# RUMBA_plus.net
KiCad netlist of a schematic drawn in Altium Designer
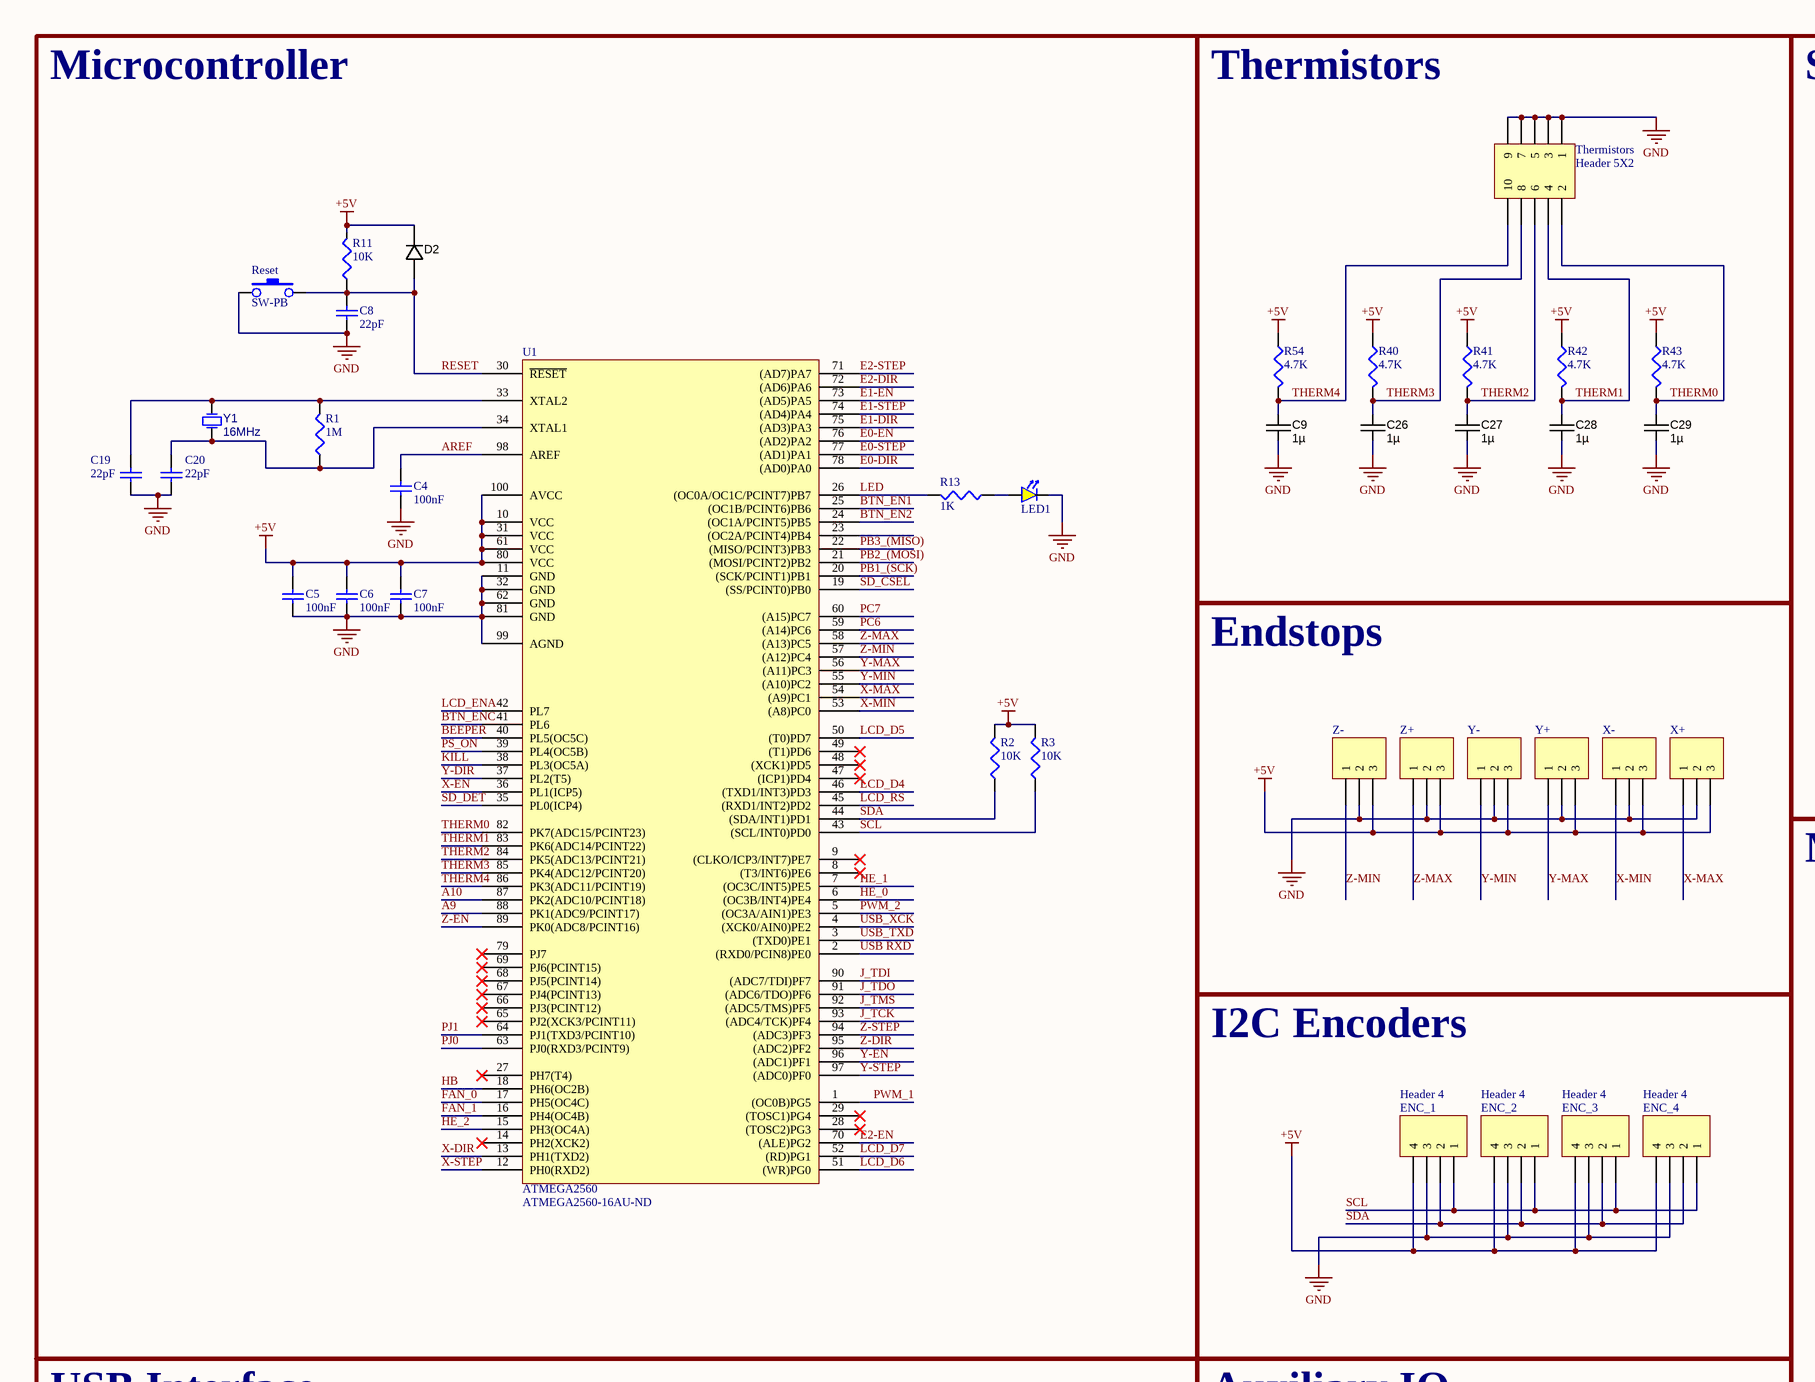
[diagram p0: RUMBA_plus.SchDoc, top left]
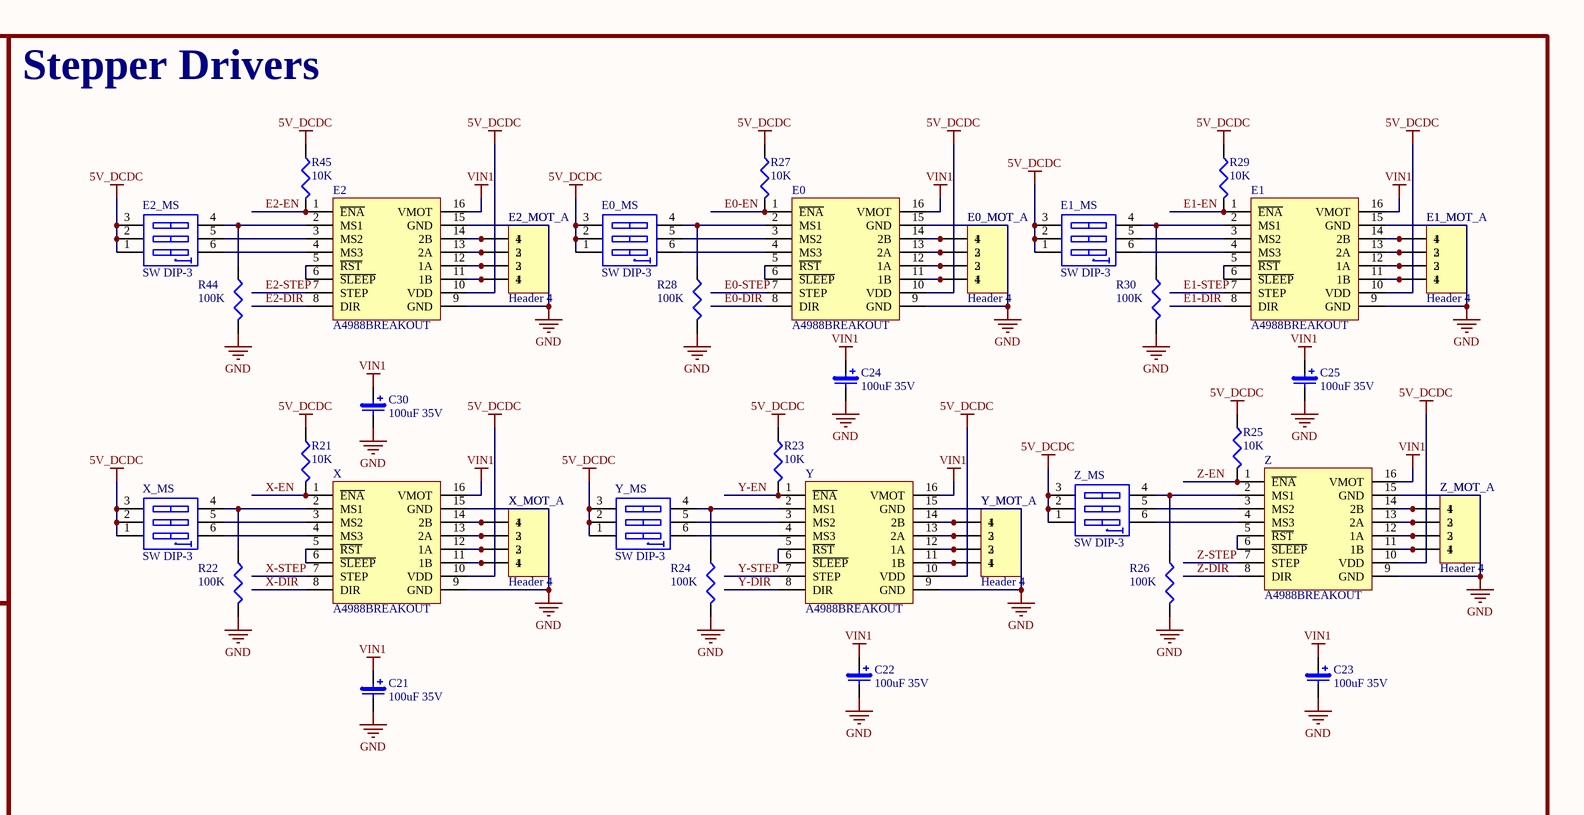
[diagram p1: RUMBA_plus.SchDoc, top right]
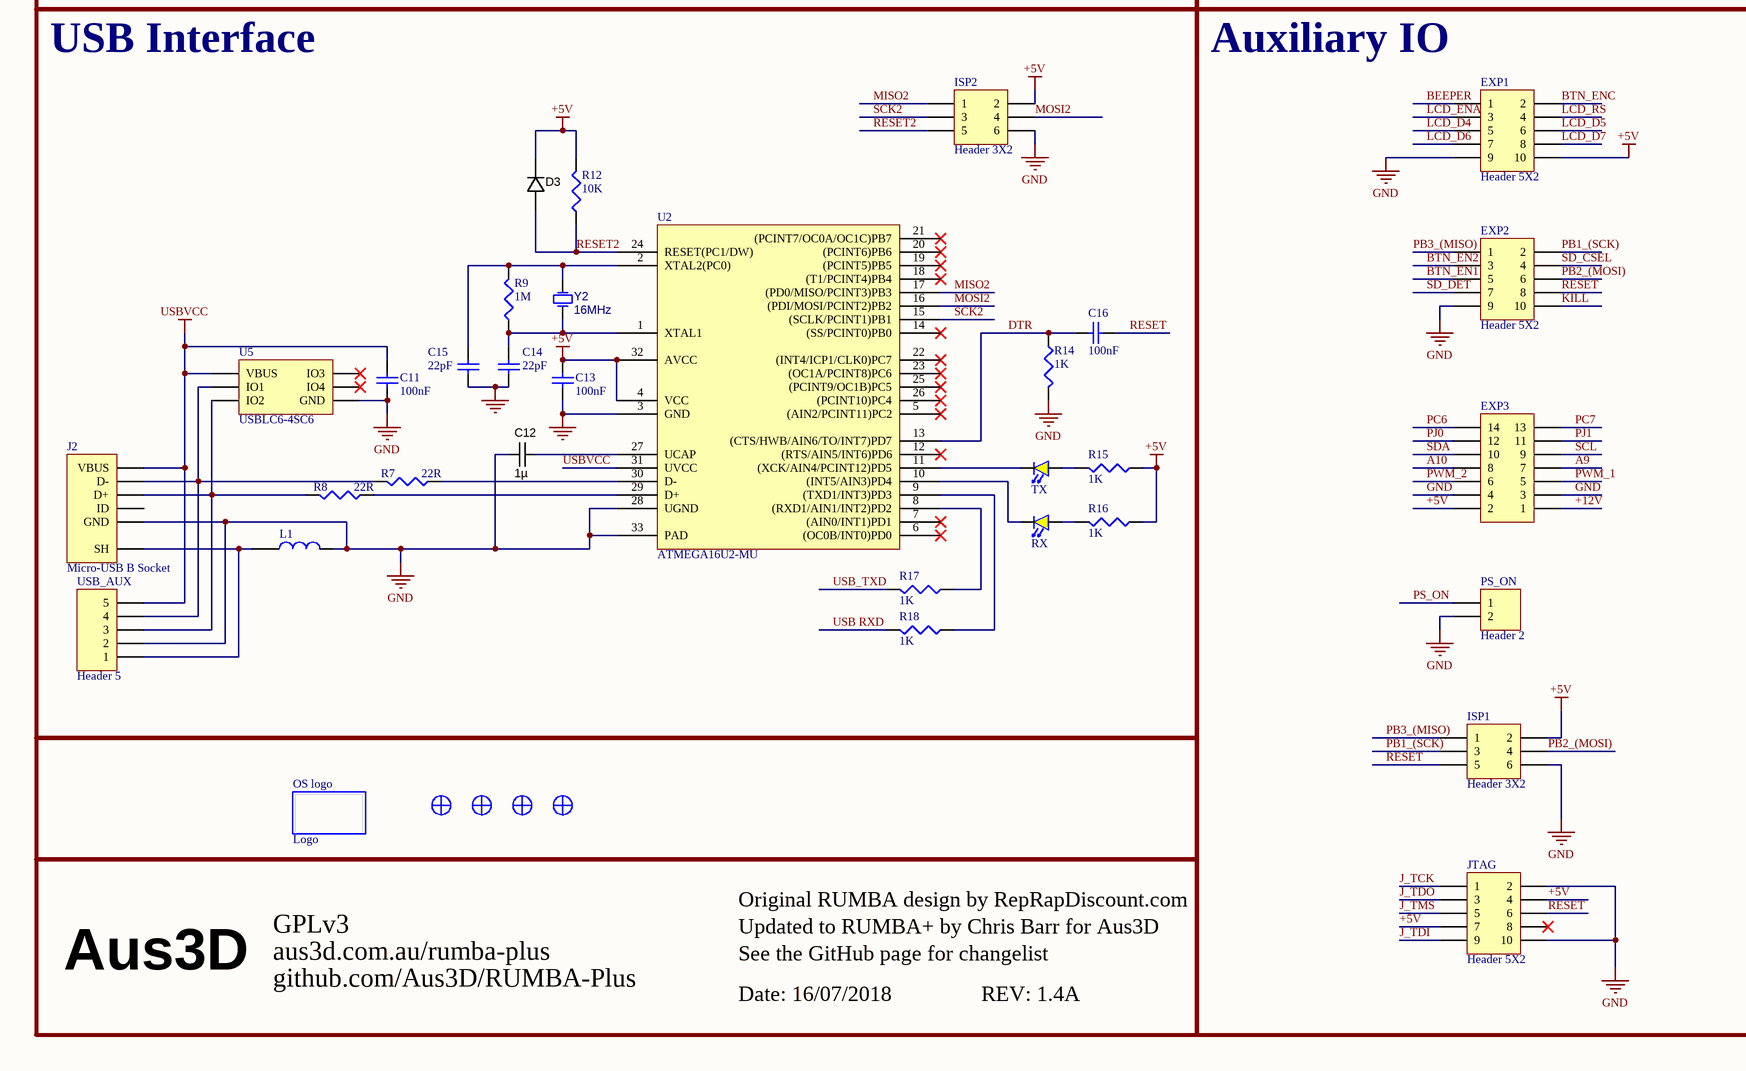
[diagram p2: RUMBA_plus.SchDoc, bottom left]
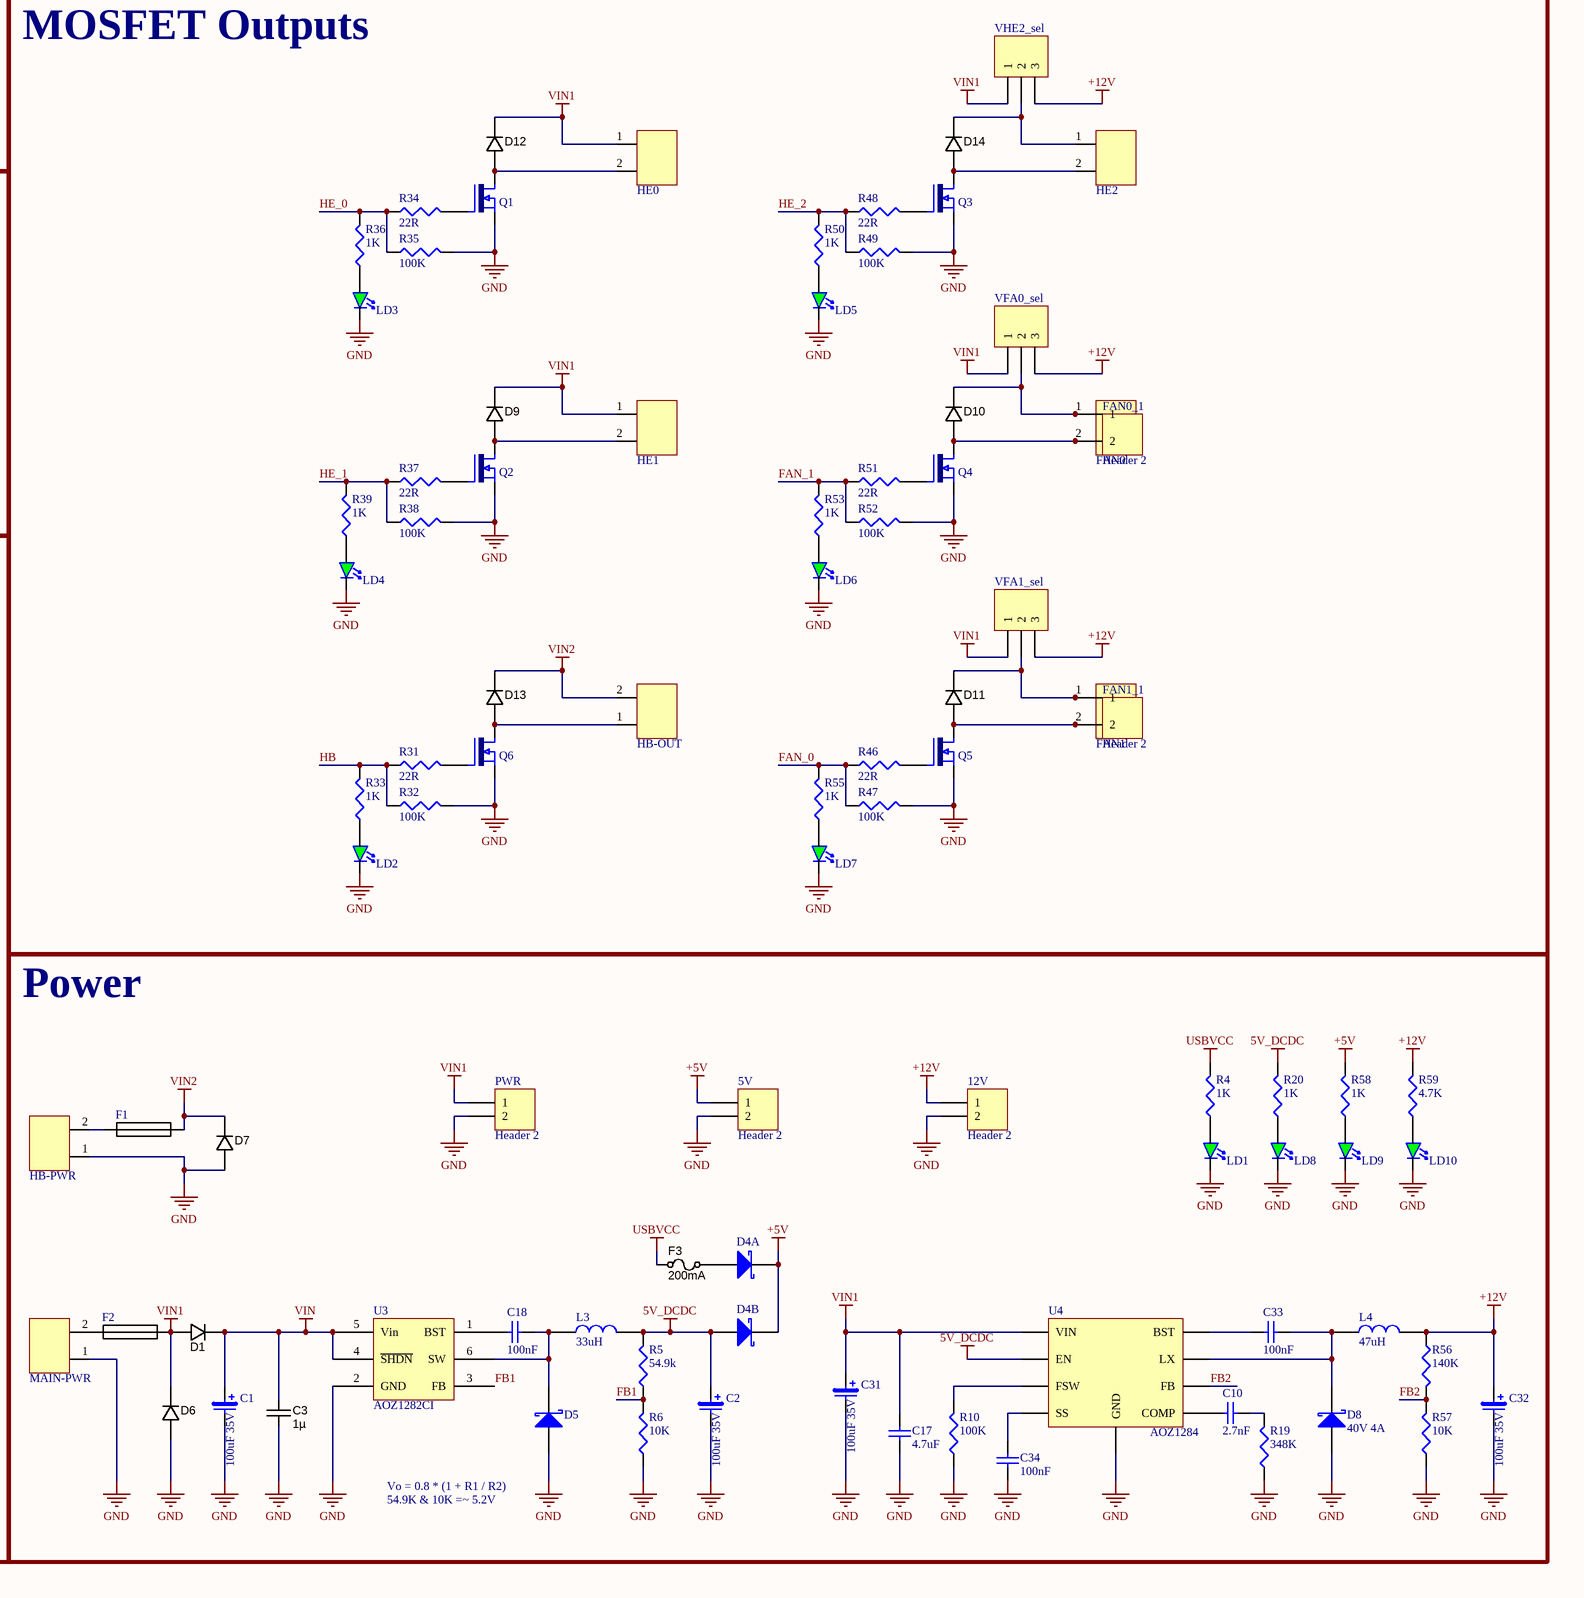
[diagram p3: RUMBA_plus.SchDoc, bottom right]

(export (version "E")
  (design (tool "Eeschema 10.0.6"))
  (components
    (comp (ref "5V")
      (value "Header 2")
      (footprint "HDR1X2")
      (description "Header, 2-Pin")
      (fields (field (name "PUBLISHER") "Altium Limited"))
      (libsource (lib "") (part "Header 2_1"))
    )
    (comp (ref "12V")
      (value "Header 2")
      (footprint "HDR1X2")
      (description "Header, 2-Pin")
      (fields (field (name "PUBLISHER") "Altium Limited"))
      (libsource (lib "") (part "Header 2_1"))
    )
    (comp (ref "C1")
      (value "100uF 35V")
      (footprint "CAP EL PANASONIC")
      (description "Polarized Capacitor (Surface Mount)")
      (fields (field (name "Comment") "CapE-6.3-100uF-35V") (field (name "PUBLISHER") "Altium Limited"))
      (libsource (lib "RUMBA_v2") (part "CapE-6.3-100uF-35V"))
    )
    (comp (ref "C2")
      (value "100uF 35V")
      (footprint "CAP EL PANASONIC")
      (description "Polarized Capacitor (Surface Mount)")
      (fields (field (name "Comment") "CapE-6.3-100uF-35V") (field (name "PUBLISHER") "Altium Limited"))
      (libsource (lib "RUMBA_v2") (part "CapE-6.3-100uF-35V"))
    )
    (comp (ref "C3")
      (value "1µ")
      (footprint "Cap 1608-0603")
      (description "Capacitor SMD Cer 1uF 10% 16V X7R 0603")
      (fields (field (name "TOLERANCE") "±10%") (field (name "Comment") "approved sub OK"))
      (libsource (lib "PBL - Capacitors") (part "CAPC_1u_0603_X7R_16V_10%"))
    )
    (comp (ref "C4")
      (value "100nF")
      (footprint "Cap 1608-0603")
      (description "Capacitor (Semiconductor SIM Model)")
      (fields (field (name "Comment") "CapC-0603-100nF") (field (name "PUBLISHER") "Altium Limited"))
      (libsource (lib "RUMBA_v2") (part "CapC-0603-100nF"))
    )
    (comp (ref "C5")
      (value "100nF")
      (footprint "Cap 1608-0603")
      (description "Capacitor (Semiconductor SIM Model)")
      (fields (field (name "Comment") "CapC-0603-100nF") (field (name "PUBLISHER") "Altium Limited"))
      (libsource (lib "RUMBA_v2") (part "CapC-0603-100nF"))
    )
    (comp (ref "C6")
      (value "100nF")
      (footprint "Cap 1608-0603")
      (description "Capacitor (Semiconductor SIM Model)")
      (fields (field (name "Comment") "CapC-0603-100nF") (field (name "PUBLISHER") "Altium Limited"))
      (libsource (lib "RUMBA_v2") (part "CapC-0603-100nF"))
    )
    (comp (ref "C7")
      (value "100nF")
      (footprint "Cap 1608-0603")
      (description "Capacitor (Semiconductor SIM Model)")
      (fields (field (name "Comment") "CapC-0603-100nF") (field (name "PUBLISHER") "Altium Limited"))
      (libsource (lib "RUMBA_v2") (part "CapC-0603-100nF"))
    )
    (comp (ref "C8")
      (value "22pF")
      (footprint "Cap 1608-0603")
      (description "Capacitor (Semiconductor SIM Model)")
      (fields (field (name "Comment") "CapC-0603-22pF") (field (name "PUBLISHER") "Altium Limited"))
      (libsource (lib "RUMBA_v2") (part "CapC-0603-22pF"))
    )
    (comp (ref "C9")
      (value "1µ")
      (footprint "Cap 1608-0603")
      (description "Capacitor SMD Cer 1uF 10% 16V X7R 0603")
      (fields (field (name "TOLERANCE") "±10%") (field (name "Comment") "approved sub OK"))
      (libsource (lib "PBL - Capacitors") (part "CAPC_1u_0603_X7R_16V_10%"))
    )
    (comp (ref "C10")
      (value "2.7nF")
      (footprint "Cap 1608-0603")
      (description "Capacitor (Semiconductor SIM Model)")
      (fields (field (name "Comment") "CapC-0603-2.7nF") (field (name "PUBLISHER") "Altium Limited"))
      (libsource (lib "RUMBA_v2") (part "CapC-0603-100nF"))
    )
    (comp (ref "C11")
      (value "100nF")
      (footprint "Cap 1608-0603")
      (description "Capacitor (Semiconductor SIM Model)")
      (fields (field (name "Comment") "CapC-0603-100nF") (field (name "PUBLISHER") "Altium Limited"))
      (libsource (lib "RUMBA_v2") (part "CapC-0603-100nF"))
    )
    (comp (ref "C12")
      (value "1µ")
      (footprint "Cap 1608-0603")
      (description "Capacitor SMD Cer 1uF 10% 16V X7R 0603")
      (fields (field (name "TOLERANCE") "±10%") (field (name "Comment") "approved sub OK"))
      (libsource (lib "PBL - Capacitors") (part "CAPC_1u_0603_X7R_16V_10%"))
    )
    (comp (ref "C13")
      (value "100nF")
      (footprint "Cap 1608-0603")
      (description "Capacitor (Semiconductor SIM Model)")
      (fields (field (name "Comment") "CapC-0603-100nF") (field (name "PUBLISHER") "Altium Limited"))
      (libsource (lib "RUMBA_v2") (part "CapC-0603-100nF"))
    )
    (comp (ref "C14")
      (value "22pF")
      (footprint "Cap 1608-0603")
      (description "Capacitor (Semiconductor SIM Model)")
      (fields (field (name "Comment") "CapC-0603-22pF") (field (name "PUBLISHER") "Altium Limited"))
      (libsource (lib "RUMBA_v2") (part "CapC-0603-22pF"))
    )
    (comp (ref "C15")
      (value "22pF")
      (footprint "Cap 1608-0603")
      (description "Capacitor (Semiconductor SIM Model)")
      (fields (field (name "Comment") "CapC-0603-22pF") (field (name "PUBLISHER") "Altium Limited"))
      (libsource (lib "RUMBA_v2") (part "CapC-0603-22pF"))
    )
    (comp (ref "C16")
      (value "100nF")
      (footprint "Cap 1608-0603")
      (description "Capacitor (Semiconductor SIM Model)")
      (fields (field (name "Comment") "CapC-0603-100nF") (field (name "PUBLISHER") "Altium Limited"))
      (libsource (lib "RUMBA_v2") (part "CapC-0603-100nF"))
    )
    (comp (ref "C17")
      (value "4.7uF")
      (footprint "CAP 3225-1210")
      (description "Capacitor (Semiconductor SIM Model)")
      (fields (field (name "Comment") "CapC-1210-4.7uF-50V") (field (name "PUBLISHER") "Altium Limited"))
      (libsource (lib "picoprint_library") (part "CapC-1210-4.7uF-50V"))
    )
    (comp (ref "C18")
      (value "100nF")
      (footprint "Cap 1608-0603")
      (description "Capacitor (Semiconductor SIM Model)")
      (fields (field (name "Comment") "CapC-0603-100nF") (field (name "PUBLISHER") "Altium Limited"))
      (libsource (lib "RUMBA_v2") (part "CapC-0603-100nF"))
    )
    (comp (ref "C19")
      (value "22pF")
      (footprint "Cap 1608-0603")
      (description "Capacitor (Semiconductor SIM Model)")
      (fields (field (name "Comment") "CapC-0603-22pF") (field (name "PUBLISHER") "Altium Limited"))
      (libsource (lib "RUMBA_v2") (part "CapC-0603-22pF"))
    )
    (comp (ref "C20")
      (value "22pF")
      (footprint "Cap 1608-0603")
      (description "Capacitor (Semiconductor SIM Model)")
      (fields (field (name "Comment") "CapC-0603-22pF") (field (name "PUBLISHER") "Altium Limited"))
      (libsource (lib "RUMBA_v2") (part "CapC-0603-22pF"))
    )
    (comp (ref "C21")
      (value "100uF 35V")
      (footprint "CAP EL PANASONIC")
      (description "Polarized Capacitor (Surface Mount)")
      (fields (field (name "Comment") "CapE-6.3-100uF-35V") (field (name "PUBLISHER") "Altium Limited"))
      (libsource (lib "RUMBA_v2") (part "CapE-6.3-100uF-35V"))
    )
    (comp (ref "C22")
      (value "100uF 35V")
      (footprint "CAP EL PANASONIC")
      (description "Polarized Capacitor (Surface Mount)")
      (fields (field (name "Comment") "CapE-6.3-100uF-35V") (field (name "PUBLISHER") "Altium Limited"))
      (libsource (lib "RUMBA_v2") (part "CapE-6.3-100uF-35V"))
    )
    (comp (ref "C23")
      (value "100uF 35V")
      (footprint "CAP EL PANASONIC")
      (description "Polarized Capacitor (Surface Mount)")
      (fields (field (name "Comment") "CapE-6.3-100uF-35V") (field (name "PUBLISHER") "Altium Limited"))
      (libsource (lib "RUMBA_v2") (part "CapE-6.3-100uF-35V"))
    )
    (comp (ref "C24")
      (value "100uF 35V")
      (footprint "CAP EL PANASONIC")
      (description "Polarized Capacitor (Surface Mount)")
      (fields (field (name "Comment") "CapE-6.3-100uF-35V") (field (name "PUBLISHER") "Altium Limited"))
      (libsource (lib "RUMBA_v2") (part "CapE-6.3-100uF-35V"))
    )
    (comp (ref "C25")
      (value "100uF 35V")
      (footprint "CAP EL PANASONIC")
      (description "Polarized Capacitor (Surface Mount)")
      (fields (field (name "Comment") "CapE-6.3-100uF-35V") (field (name "PUBLISHER") "Altium Limited"))
      (libsource (lib "RUMBA_v2") (part "CapE-6.3-100uF-35V"))
    )
    (comp (ref "C26")
      (value "1µ")
      (footprint "Cap 1608-0603")
      (description "Capacitor SMD Cer 1uF 10% 16V X7R 0603")
      (fields (field (name "TOLERANCE") "±10%") (field (name "Comment") "approved sub OK"))
      (libsource (lib "PBL - Capacitors") (part "CAPC_1u_0603_X7R_16V_10%"))
    )
    (comp (ref "C27")
      (value "1µ")
      (footprint "Cap 1608-0603")
      (description "Capacitor SMD Cer 1uF 10% 16V X7R 0603")
      (fields (field (name "TOLERANCE") "±10%") (field (name "Comment") "approved sub OK"))
      (libsource (lib "PBL - Capacitors") (part "CAPC_1u_0603_X7R_16V_10%"))
    )
    (comp (ref "C28")
      (value "1µ")
      (footprint "Cap 1608-0603")
      (description "Capacitor SMD Cer 1uF 10% 16V X7R 0603")
      (fields (field (name "TOLERANCE") "±10%") (field (name "Comment") "approved sub OK"))
      (libsource (lib "PBL - Capacitors") (part "CAPC_1u_0603_X7R_16V_10%"))
    )
    (comp (ref "C29")
      (value "1µ")
      (footprint "Cap 1608-0603")
      (description "Capacitor SMD Cer 1uF 10% 16V X7R 0603")
      (fields (field (name "TOLERANCE") "±10%") (field (name "Comment") "approved sub OK"))
      (libsource (lib "PBL - Capacitors") (part "CAPC_1u_0603_X7R_16V_10%"))
    )
    (comp (ref "C30")
      (value "100uF 35V")
      (footprint "CAP EL PANASONIC")
      (description "Polarized Capacitor (Surface Mount)")
      (fields (field (name "Comment") "CapE-6.3-100uF-35V") (field (name "PUBLISHER") "Altium Limited"))
      (libsource (lib "RUMBA_v2") (part "CapE-6.3-100uF-35V"))
    )
    (comp (ref "C31")
      (value "100uF 35V")
      (footprint "CAP EL PANASONIC")
      (description "Polarized Capacitor (Surface Mount)")
      (fields (field (name "Comment") "CapE-6.3-100uF-35V") (field (name "PUBLISHER") "Altium Limited"))
      (libsource (lib "RUMBA_v2") (part "CapE-6.3-100uF-35V"))
    )
    (comp (ref "C32")
      (value "100uF 35V")
      (footprint "CAP EL PANASONIC")
      (description "Polarized Capacitor (Surface Mount)")
      (fields (field (name "Comment") "CapE-6.3-100uF-35V") (field (name "PUBLISHER") "Altium Limited"))
      (libsource (lib "RUMBA_v2") (part "CapE-6.3-100uF-35V"))
    )
    (comp (ref "C33")
      (value "100nF")
      (footprint "Cap 1608-0603")
      (description "Capacitor (Semiconductor SIM Model)")
      (fields (field (name "Comment") "CapC-0603-100nF") (field (name "PUBLISHER") "Altium Limited"))
      (libsource (lib "RUMBA_v2") (part "CapC-0603-100nF"))
    )
    (comp (ref "C34")
      (value "100nF")
      (footprint "Cap 1608-0603")
      (description "Capacitor (Semiconductor SIM Model)")
      (fields (field (name "Comment") "CapC-0603-100nF") (field (name "PUBLISHER") "Altium Limited"))
      (libsource (lib "RUMBA_v2") (part "CapC-0603-100nF"))
    )
    (comp (ref "D1")
      (value "100V; 1.5A")
      (footprint "DO-214AC")
      (description "Diode SMD 100V 1.5A SMA")
      (libsource (lib "PBL - Diodes") (part "DIODE_100V_1.5A_SMA"))
    )
    (comp (ref "D2")
      (value "DIODE_75V_500mW")
      (footprint "SOD323")
      (description "Diode SMD 300mA 0.5W SOD323")
      (fields
        (field (name "MANUFACTURER") "Micro Commercial Co")
        (field (name "MANUFACTURER PART NUMBER") "1N4148WX-TP")
      )
      (libsource (lib "PBL - Diodes") (part "DIODE_75V_500mW"))
    )
    (comp (ref "D3")
      (value "DIODE_75V_500mW")
      (footprint "SOD323")
      (description "Diode SMD 300mA 0.5W SOD323")
      (fields
        (field (name "MANUFACTURER") "Micro Commercial Co")
        (field (name "MANUFACTURER PART NUMBER") "1N4148WX-TP")
      )
      (libsource (lib "PBL - Diodes") (part "DIODE_75V_500mW"))
    )
    (comp (ref "D4")
      (value "Diode Schottky 2A 20V Dual Common Cathode")
      (footprint "SOT1061")
      (description "Default Diode")
      (fields (field (name "PUBLISHER") "Altium Limited"))
      (libsource (lib "RUMBA_v2") (part "Diode Schottky 2A 20V Dual Common Cathode"))
    )
    (comp (ref "D5")
      (value "Diode Schottky 2A 40V")
      (footprint "DIOM2616X08N")
      (description "Default Diode")
      (fields (field (name "PUBLISHER") "Altium Limited"))
      (libsource (lib "picoprint_library") (part "Diode Schottky 2A 40V"))
    )
    (comp (ref "D6")
      (value "100V; 1.5A")
      (footprint "DO-214AC")
      (description "Diode SMD 100V 1.5A SMA")
      (libsource (lib "PBL - Diodes") (part "DIODE_100V_1.5A_SMA"))
    )
    (comp (ref "D7")
      (value "100V; 1.5A")
      (footprint "DO-214AC")
      (description "Diode SMD 100V 1.5A SMA")
      (libsource (lib "PBL - Diodes") (part "DIODE_100V_1.5A_SMA"))
    )
    (comp (ref "D8")
      (value "40V 4A")
      (footprint "DO-214AA")
      (description "Schottky Diode")
      (fields (field (name "Comment") "Diode SSB44-E3") (field (name "PUBLISHER") "Altium Limited"))
      (libsource (lib "RUMBA_library") (part "Diode Schottky - 40V 4A - SSB44-E3"))
    )
    (comp (ref "D9")
      (value "100V; 1.5A")
      (footprint "DO-214AC")
      (description "Diode SMD 100V 1.5A SMA")
      (libsource (lib "PBL - Diodes") (part "DIODE_100V_1.5A_SMA"))
    )
    (comp (ref "D10")
      (value "100V; 1.5A")
      (footprint "DO-214AC")
      (description "Diode SMD 100V 1.5A SMA")
      (libsource (lib "PBL - Diodes") (part "DIODE_100V_1.5A_SMA"))
    )
    (comp (ref "D11")
      (value "100V; 1.5A")
      (footprint "DO-214AC")
      (description "Diode SMD 100V 1.5A SMA")
      (libsource (lib "PBL - Diodes") (part "DIODE_100V_1.5A_SMA"))
    )
    (comp (ref "D12")
      (value "100V; 1.5A")
      (footprint "DO-214AC")
      (description "Diode SMD 100V 1.5A SMA")
      (libsource (lib "PBL - Diodes") (part "DIODE_100V_1.5A_SMA"))
    )
    (comp (ref "D13")
      (value "100V; 1.5A")
      (footprint "DO-214AC")
      (description "Diode SMD 100V 1.5A SMA")
      (libsource (lib "PBL - Diodes") (part "DIODE_100V_1.5A_SMA"))
    )
    (comp (ref "D14")
      (value "100V; 1.5A")
      (footprint "DO-214AC")
      (description "Diode SMD 100V 1.5A SMA")
      (libsource (lib "PBL - Diodes") (part "DIODE_100V_1.5A_SMA"))
    )
    (comp (ref "E0")
      (value "A4988BREAKOUT")
      (footprint "A4988BREAKOUT")
      (libsource (lib "RUMBA_v2") (part "A4988BREAKOUT"))
    )
    (comp (ref "E0_MOT")
      (value "ScrewTerminal-3.5mm-4Way")
      (footprint "TERM4 3.5mm")
      (description "Screw Terminal 3.5mm 4-Way")
      (fields (field (name "PUBLISHER") "Altium Limited"))
      (libsource (lib "RUMBA_v2") (part "ScrewTerminal-3.5mm-4Way"))
    )
    (comp (ref "E0_MOT_A")
      (value "Header 4")
      (footprint "HDR1X4")
      (description "Header, 4-Pin")
      (fields (field (name "PUBLISHER") "Altium Limited"))
      (libsource (lib "RUMBA_v2") (part "Header 4_1"))
    )
    (comp (ref "E0_MS")
      (value "SW DIP-3")
      (footprint "dipsw SO6")
      (description "DIP Switch")
      (fields (field (name "PUBLISHER") "Altium Limited"))
      (libsource (lib "RUMBA_v2") (part "SW DIP-3"))
    )
    (comp (ref "E1")
      (value "A4988BREAKOUT")
      (footprint "A4988BREAKOUT")
      (libsource (lib "RUMBA_v2") (part "A4988BREAKOUT"))
    )
    (comp (ref "E1_MOT")
      (value "ScrewTerminal-3.5mm-4Way")
      (footprint "TERM4 3.5mm")
      (description "Screw Terminal 3.5mm 4-Way")
      (fields (field (name "PUBLISHER") "Altium Limited"))
      (libsource (lib "RUMBA_v2") (part "ScrewTerminal-3.5mm-4Way"))
    )
    (comp (ref "E1_MOT_A")
      (value "Header 4")
      (footprint "HDR1X4")
      (description "Header, 4-Pin")
      (fields (field (name "PUBLISHER") "Altium Limited"))
      (libsource (lib "RUMBA_v2") (part "Header 4_1"))
    )
    (comp (ref "E1_MS")
      (value "SW DIP-3")
      (footprint "dipsw SO6")
      (description "DIP Switch")
      (fields (field (name "PUBLISHER") "Altium Limited"))
      (libsource (lib "RUMBA_v2") (part "SW DIP-3"))
    )
    (comp (ref "E2")
      (value "A4988BREAKOUT")
      (footprint "A4988BREAKOUT")
      (libsource (lib "RUMBA_v2") (part "A4988BREAKOUT"))
    )
    (comp (ref "E2_MOT")
      (value "ScrewTerminal-3.5mm-4Way")
      (footprint "TERM4 3.5mm")
      (description "Screw Terminal 3.5mm 4-Way")
      (fields (field (name "PUBLISHER") "Altium Limited"))
      (libsource (lib "RUMBA_v2") (part "ScrewTerminal-3.5mm-4Way"))
    )
    (comp (ref "E2_MOT_A")
      (value "Header 4")
      (footprint "HDR1X4")
      (description "Header, 4-Pin")
      (fields (field (name "PUBLISHER") "Altium Limited"))
      (libsource (lib "RUMBA_v2") (part "Header 4_1"))
    )
    (comp (ref "E2_MS")
      (value "SW DIP-3")
      (footprint "dipsw SO6")
      (description "DIP Switch")
      (fields (field (name "PUBLISHER") "Altium Limited"))
      (libsource (lib "RUMBA_v2") (part "SW DIP-3"))
    )
    (comp (ref "ENC_1")
      (value "Header 4")
      (footprint "HDR1X4")
      (description "Header, 4-Pin")
      (fields (field (name "PUBLISHER") "Altium Limited"))
      (libsource (lib "Miscellaneous Connectors") (part "Header 4"))
    )
    (comp (ref "ENC_2")
      (value "Header 4")
      (footprint "HDR1X4")
      (description "Header, 4-Pin")
      (fields (field (name "PUBLISHER") "Altium Limited"))
      (libsource (lib "Miscellaneous Connectors") (part "Header 4"))
    )
    (comp (ref "ENC_3")
      (value "Header 4")
      (footprint "HDR1X4")
      (description "Header, 4-Pin")
      (fields (field (name "PUBLISHER") "Altium Limited"))
      (libsource (lib "Miscellaneous Connectors") (part "Header 4"))
    )
    (comp (ref "ENC_4")
      (value "Header 4")
      (footprint "HDR1X4")
      (description "Header, 4-Pin")
      (fields (field (name "PUBLISHER") "Altium Limited"))
      (libsource (lib "Miscellaneous Connectors") (part "Header 4"))
    )
    (comp (ref "EXP1")
      (value "Header 5X2")
      (footprint "HDR2X5_exp Iner only\\")
      (description "Header, 5-Pin, Dual row")
      (fields (field (name "PUBLISHER") "Altium Limited"))
      (libsource (lib "RUMBA_v2") (part "Header 5X2"))
    )
    (comp (ref "EXP2")
      (value "Header 5X2")
      (footprint "HDR2X5_exp Iner only\\")
      (description "Header, 5-Pin, Dual row")
      (fields (field (name "PUBLISHER") "Altium Limited"))
      (libsource (lib "RUMBA_v2") (part "Header 5X2"))
    )
    (comp (ref "EXP3")
      (value "Header 7X2")
      (footprint "HDR2X7")
      (description "Header, 7-Pin, Dual row")
      (fields (field (name "PUBLISHER") "Altium Limited"))
      (libsource (lib "RUMBA_v2") (part "Header 7X2"))
    )
    (comp (ref "F1")
      (value "Fuseholder - Mini ATC ATO 15A")
      (footprint "Fuseholder - BK-6013 - Mini ATC ATO Blade 15A")
      (libsource (lib "Schlib1") (part "Fuseholder - Mini ATC ATO 15A"))
    )
    (comp (ref "F2")
      (value "Fuseholder - Mini ATC ATO 15A")
      (footprint "Fuseholder - BK-6013 - Mini ATC ATO Blade 15A")
      (libsource (lib "Schlib1") (part "Fuseholder - Mini ATC ATO 15A"))
    )
    (comp (ref "F3")
      (value "200mA")
      (footprint "PTC Fuse1608-0603")
      (description "Fuse - 15V 200mA Trip PTC SMD 0603")
      (fields (field (name "Comment") "PTC Resettable Fuse"))
      (libsource (lib "Schlib1") (part "Fuse - 15V 200mA Trip PTC SMD 0603"))
    )
    (comp (ref "FAN0")
      (value "Screw Terminal 3.5mm 2-Way")
      (footprint "TERM2 3.5mm")
      (libsource (lib "RUMBA_v2") (part "ScrewTerminal-3.5mm-2Way"))
    )
    (comp (ref "FAN0_1")
      (value "Header 2")
      (footprint "HDR1X2")
      (description "Header, 2-Pin")
      (fields (field (name "PUBLISHER") "Altium Limited"))
      (libsource (lib "RUMBA_v2") (part "Header 2"))
    )
    (comp (ref "FAN1")
      (value "Screw Terminal 3.5mm 2-Way")
      (footprint "TERM2 3.5mm")
      (libsource (lib "RUMBA_v2") (part "ScrewTerminal-3.5mm-2Way"))
    )
    (comp (ref "FAN1_1")
      (value "Header 2")
      (footprint "HDR1X2")
      (description "Header, 2-Pin")
      (fields (field (name "PUBLISHER") "Altium Limited"))
      (libsource (lib "RUMBA_v2") (part "Header 2"))
    )
    (comp (ref "HB-OUT")
      (value "Screw Terminal 5mm 2-Way")
      (footprint "TERM2 5MM")
      (libsource (lib "") (part "ScrewTerminal-5mm-2Way_1"))
    )
    (comp (ref "HB-PWR")
      (value "Screw Terminal 5mm 2-Way")
      (footprint "TERM2 5MM")
      (libsource (lib "RUMBA_v2") (part "ScrewTerminal-5mm-2Way"))
    )
    (comp (ref "HE0")
      (value "Screw Terminal 3.5mm 2-Way")
      (footprint "TERM2 3.5mm")
      (libsource (lib "RUMBA_v2") (part "ScrewTerminal-3.5mm-2Way"))
    )
    (comp (ref "HE1")
      (value "Screw Terminal 3.5mm 2-Way")
      (footprint "TERM2 3.5mm")
      (libsource (lib "RUMBA_v2") (part "ScrewTerminal-3.5mm-2Way"))
    )
    (comp (ref "HE2")
      (value "Screw Terminal 3.5mm 2-Way")
      (footprint "TERM2 3.5mm")
      (libsource (lib "RUMBA_v2") (part "ScrewTerminal-3.5mm-2Way"))
    )
    (comp (ref "ISP1")
      (value "Header 3X2")
      (footprint "HDR2X3")
      (description "Header, 3-Pin, Dual row")
      (fields (field (name "PUBLISHER") "Altium Limited"))
      (libsource (lib "RUMBA_v2") (part "Header 3X2"))
    )
    (comp (ref "ISP2")
      (value "Header 3X2")
      (footprint "HDR2X3")
      (description "Header, 3-Pin, Dual row")
      (fields (field (name "PUBLISHER") "Altium Limited"))
      (libsource (lib "RUMBA_v2") (part "Header 3X2"))
    )
    (comp (ref "J2")
      (value "Micro-USB B Socket")
      (footprint "Micro-USB B Molex 105017-0001")
      (libsource (lib "picoprint_library") (part "Micro-USB B Socket"))
    )
    (comp (ref "JTAG")
      (value "Header 5X2")
      (footprint "HDR2X5")
      (description "Header, 5-Pin, Dual row")
      (fields (field (name "PUBLISHER") "Altium Limited"))
      (libsource (lib "RUMBA_v2") (part "Header 5X2"))
    )
    (comp (ref "L1")
      (value "Ferrite Bead SMD 0805")
      (footprint "Res 2012-0805")
      (description "MagneticCore Inductor with Winding Polarity Marking")
      (fields (field (name "PUBLISHER") "Altium Limited"))
      (libsource (lib "RUMBA_v2") (part "Ferrite Bead SMD 0805"))
    )
    (comp (ref "L3")
      (value "33uH")
      (footprint "SRN6045TA SMD Inductor")
      (description "MagneticCore Inductor with Winding Polarity Marking")
      (fields (field (name "Comment") "Inductor SMD 33uH 2.5A") (field (name "PUBLISHER") "Altium Limited"))
      (libsource (lib "RUMBA_v2") (part "Inductor SMD 33uH 2.5A"))
    )
    (comp (ref "L4")
      (value "47uH")
      (footprint "SRN8040TA SMD Inductor")
      (description "MagneticCore Inductor with Winding Polarity Marking")
      (fields (field (name "Comment") "Inductor SMD 47uH 2.2A") (field (name "PUBLISHER") "Altium Limited"))
      (libsource (lib "RUMBA_v2") (part "Inductor SMD 47uH 2.2A"))
    )
    (comp (ref "LD1")
      (value "GREEN")
      (footprint "LED 1608-0603")
      (description "Hyper-Bright LED")
      (libsource (lib "picoprint_library") (part "LEDG  0603"))
    )
    (comp (ref "LD2")
      (value "GREEN")
      (footprint "LED 1608-0603")
      (description "Hyper-Bright LED")
      (libsource (lib "picoprint_library") (part "LEDG  0603"))
    )
    (comp (ref "LD3")
      (value "GREEN")
      (footprint "LED 1608-0603")
      (description "Hyper-Bright LED")
      (libsource (lib "picoprint_library") (part "LEDG  0603"))
    )
    (comp (ref "LD4")
      (value "GREEN")
      (footprint "LED 1608-0603")
      (description "Hyper-Bright LED")
      (libsource (lib "picoprint_library") (part "LEDG  0603"))
    )
    (comp (ref "LD5")
      (value "GREEN")
      (footprint "LED 1608-0603")
      (description "Hyper-Bright LED")
      (libsource (lib "picoprint_library") (part "LEDG  0603"))
    )
    (comp (ref "LD6")
      (value "GREEN")
      (footprint "LED 1608-0603")
      (description "Hyper-Bright LED")
      (libsource (lib "picoprint_library") (part "LEDG  0603"))
    )
    (comp (ref "LD7")
      (value "GREEN")
      (footprint "LED 1608-0603")
      (description "Hyper-Bright LED")
      (libsource (lib "picoprint_library") (part "LEDG  0603"))
    )
    (comp (ref "LD8")
      (value "GREEN")
      (footprint "LED 1608-0603")
      (description "Hyper-Bright LED")
      (libsource (lib "picoprint_library") (part "LEDG  0603"))
    )
    (comp (ref "LD9")
      (value "GREEN")
      (footprint "LED 1608-0603")
      (description "Hyper-Bright LED")
      (libsource (lib "picoprint_library") (part "LEDG  0603"))
    )
    (comp (ref "LD10")
      (value "GREEN")
      (footprint "LED 1608-0603")
      (description "Hyper-Bright LED")
      (libsource (lib "picoprint_library") (part "LEDG  0603"))
    )
    (comp (ref "LED1")
      (value "YELLOW")
      (footprint "LED 1608-0603")
      (description "Hyper-Bright LED")
      (libsource (lib "picoprint_library") (part "LEDY  0603"))
    )
    (comp (ref "MAIN-PWR")
      (value "Screw Terminal 5mm 2-Way")
      (footprint "TERM2 5MM")
      (libsource (lib "RUMBA_v2") (part "ScrewTerminal-5mm-2Way"))
    )
    (comp (ref "OS logo") (value "Logo") (footprint "OS LOGO TOP") (libsource (lib "gc") (part "Logo")))
    (comp (ref "PS_ON")
      (value "Header 2")
      (footprint "HDR1X2")
      (description "Header, 2-Pin")
      (fields (field (name "PUBLISHER") "Altium Limited"))
      (libsource (lib "") (part "Header 2_1"))
    )
    (comp (ref "PWR")
      (value "Header 2")
      (footprint "HDR1X2")
      (description "Header, 2-Pin")
      (fields (field (name "PUBLISHER") "Altium Limited"))
      (libsource (lib "") (part "Header 2_1"))
    )
    (comp (ref "Q1")
      (value "BUK9Y21-40E")
      (footprint "LFPACK")
      (libsource (lib "RUMBA_library") (part "MOSFET - BUK9Y21-40E"))
    )
    (comp (ref "Q2")
      (value "BUK9Y21-40E")
      (footprint "LFPACK")
      (libsource (lib "RUMBA_library") (part "MOSFET - BUK9Y21-40E"))
    )
    (comp (ref "Q3")
      (value "BUK9Y21-40E")
      (footprint "LFPACK")
      (libsource (lib "RUMBA_library") (part "MOSFET - BUK9Y21-40E"))
    )
    (comp (ref "Q4")
      (value "BUK9Y21-40E")
      (footprint "LFPACK")
      (libsource (lib "RUMBA_library") (part "MOSFET - BUK9Y21-40E"))
    )
    (comp (ref "Q5")
      (value "BUK9Y21-40E")
      (footprint "LFPACK")
      (libsource (lib "RUMBA_library") (part "MOSFET - BUK9Y21-40E"))
    )
    (comp (ref "Q6")
      (value "PSMN1R8-40YLC")
      (footprint "LFPACK")
      (libsource (lib "RUMBA_library") (part "MOSFET - PSMN1R8-40YLC"))
    )
    (comp (ref "R1")
      (value "1M")
      (footprint "RES 1608-0603")
      (description "Resistor")
      (fields (field (name "Comment") "Res-0603-1M") (field (name "PUBLISHER") "Altium Limited"))
      (libsource (lib "RUMBA_v2") (part "Res-0603-1M"))
    )
    (comp (ref "R2")
      (value "10K")
      (footprint "RES 1608-0603")
      (description "Resistor")
      (fields (field (name "Comment") "Res-0603-10K") (field (name "PUBLISHER") "Altium Limited"))
      (libsource (lib "RUMBA_v2") (part "Res-0603-10K"))
    )
    (comp (ref "R3")
      (value "10K")
      (footprint "RES 1608-0603")
      (description "Resistor")
      (fields (field (name "Comment") "Res-0603-10K") (field (name "PUBLISHER") "Altium Limited"))
      (libsource (lib "RUMBA_v2") (part "Res-0603-10K"))
    )
    (comp (ref "R4")
      (value "1K")
      (footprint "RES 1608-0603")
      (description "Resistor")
      (fields (field (name "Comment") "Res-0603-1K") (field (name "PUBLISHER") "Altium Limited"))
      (libsource (lib "RUMBA_v2") (part "Res-0603-1K"))
    )
    (comp (ref "R5")
      (value "54.9k")
      (footprint "RES 1608-0603")
      (description "Resistor")
      (fields (field (name "Comment") "Res-0603-54K9") (field (name "PUBLISHER") "Altium Limited"))
      (libsource (lib "RUMBA_v2") (part "Res-0603-10K"))
    )
    (comp (ref "R6")
      (value "10K")
      (footprint "RES 1608-0603")
      (description "Resistor")
      (fields (field (name "Comment") "Res-0603-10K") (field (name "PUBLISHER") "Altium Limited"))
      (libsource (lib "RUMBA_v2") (part "Res-0603-10K"))
    )
    (comp (ref "R7")
      (value "22R")
      (footprint "RES 1608-0603")
      (description "Resistor")
      (fields (field (name "Comment") "Res-0603-22R") (field (name "PUBLISHER") "Altium Limited"))
      (libsource (lib "RUMBA_v2") (part "Res-0603-22R"))
    )
    (comp (ref "R8")
      (value "22R")
      (footprint "RES 1608-0603")
      (description "Resistor")
      (fields (field (name "Comment") "Res-0603-22R") (field (name "PUBLISHER") "Altium Limited"))
      (libsource (lib "RUMBA_v2") (part "Res-0603-22R"))
    )
    (comp (ref "R9")
      (value "1M")
      (footprint "RES 1608-0603")
      (description "Resistor")
      (fields (field (name "Comment") "Res-0603-1M") (field (name "PUBLISHER") "Altium Limited"))
      (libsource (lib "RUMBA_v2") (part "Res-0603-1M"))
    )
    (comp (ref "R10")
      (value "100K")
      (footprint "RES 1608-0603")
      (description "Resistor")
      (fields (field (name "Comment") "Res-0603-100K") (field (name "PUBLISHER") "Altium Limited"))
      (libsource (lib "RUMBA_v2") (part "Res-0603-100K"))
    )
    (comp (ref "R11")
      (value "10K")
      (footprint "RES 1608-0603")
      (description "Resistor")
      (fields (field (name "Comment") "Res-0603-10K") (field (name "PUBLISHER") "Altium Limited"))
      (libsource (lib "RUMBA_v2") (part "Res-0603-10K"))
    )
    (comp (ref "R12")
      (value "10K")
      (footprint "RES 1608-0603")
      (description "Resistor")
      (fields (field (name "Comment") "Res-0603-10K") (field (name "PUBLISHER") "Altium Limited"))
      (libsource (lib "RUMBA_v2") (part "Res-0603-10K"))
    )
    (comp (ref "R13")
      (value "1K")
      (footprint "RES 1608-0603")
      (description "Resistor")
      (fields (field (name "Comment") "Res-0603-1K") (field (name "PUBLISHER") "Altium Limited"))
      (libsource (lib "RUMBA_v2") (part "Res-0603-1K"))
    )
    (comp (ref "R14")
      (value "1K")
      (footprint "RES 1608-0603")
      (description "Resistor")
      (fields (field (name "Comment") "Res-0603-1K") (field (name "PUBLISHER") "Altium Limited"))
      (libsource (lib "RUMBA_v2") (part "Res-0603-1K"))
    )
    (comp (ref "R15")
      (value "1K")
      (footprint "RES 1608-0603")
      (description "Resistor")
      (fields (field (name "Comment") "Res-0603-1K") (field (name "PUBLISHER") "Altium Limited"))
      (libsource (lib "RUMBA_v2") (part "Res-0603-1K"))
    )
    (comp (ref "R16")
      (value "1K")
      (footprint "RES 1608-0603")
      (description "Resistor")
      (fields (field (name "Comment") "Res-0603-1K") (field (name "PUBLISHER") "Altium Limited"))
      (libsource (lib "RUMBA_v2") (part "Res-0603-1K"))
    )
    (comp (ref "R17")
      (value "1K")
      (footprint "RES 1608-0603")
      (description "Resistor")
      (fields (field (name "Comment") "Res-0603-1K") (field (name "PUBLISHER") "Altium Limited"))
      (libsource (lib "RUMBA_v2") (part "Res-0603-1K"))
    )
    (comp (ref "R18")
      (value "1K")
      (footprint "RES 1608-0603")
      (description "Resistor")
      (fields (field (name "Comment") "Res-0603-1K") (field (name "PUBLISHER") "Altium Limited"))
      (libsource (lib "RUMBA_v2") (part "Res-0603-1K"))
    )
    (comp (ref "R19")
      (value "348K")
      (footprint "RES 1608-0603")
      (description "Resistor")
      (fields (field (name "Comment") "Res-0603-348K") (field (name "PUBLISHER") "Altium Limited"))
      (libsource (lib "RUMBA_v2") (part "Res-0603-53.6K"))
    )
    (comp (ref "R20")
      (value "1K")
      (footprint "RES 1608-0603")
      (description "Resistor")
      (fields (field (name "Comment") "Res-0603-1K") (field (name "PUBLISHER") "Altium Limited"))
      (libsource (lib "RUMBA_v2") (part "Res-0603-1K"))
    )
    (comp (ref "R21")
      (value "10K")
      (footprint "RES 1608-0603")
      (description "Resistor")
      (fields (field (name "Comment") "Res-0603-10K") (field (name "PUBLISHER") "Altium Limited"))
      (libsource (lib "RUMBA_v2") (part "Res-0603-10K"))
    )
    (comp (ref "R22")
      (value "100K")
      (footprint "RES 1608-0603")
      (description "Resistor")
      (fields (field (name "Comment") "Res-0603-100K") (field (name "PUBLISHER") "Altium Limited"))
      (libsource (lib "RUMBA_v2") (part "Res-0603-100K"))
    )
    (comp (ref "R23")
      (value "10K")
      (footprint "RES 1608-0603")
      (description "Resistor")
      (fields (field (name "Comment") "Res-0603-10K") (field (name "PUBLISHER") "Altium Limited"))
      (libsource (lib "RUMBA_v2") (part "Res-0603-10K"))
    )
    (comp (ref "R24")
      (value "100K")
      (footprint "RES 1608-0603")
      (description "Resistor")
      (fields (field (name "Comment") "Res-0603-100K") (field (name "PUBLISHER") "Altium Limited"))
      (libsource (lib "RUMBA_v2") (part "Res-0603-100K"))
    )
    (comp (ref "R25")
      (value "10K")
      (footprint "RES 1608-0603")
      (description "Resistor")
      (fields (field (name "Comment") "Res-0603-10K") (field (name "PUBLISHER") "Altium Limited"))
      (libsource (lib "RUMBA_v2") (part "Res-0603-10K"))
    )
    (comp (ref "R26")
      (value "100K")
      (footprint "RES 1608-0603")
      (description "Resistor")
      (fields (field (name "Comment") "Res-0603-100K") (field (name "PUBLISHER") "Altium Limited"))
      (libsource (lib "RUMBA_v2") (part "Res-0603-100K"))
    )
    (comp (ref "R27")
      (value "10K")
      (footprint "RES 1608-0603")
      (description "Resistor")
      (fields (field (name "Comment") "Res-0603-10K") (field (name "PUBLISHER") "Altium Limited"))
      (libsource (lib "RUMBA_v2") (part "Res-0603-10K"))
    )
    (comp (ref "R28")
      (value "100K")
      (footprint "RES 1608-0603")
      (description "Resistor")
      (fields (field (name "Comment") "Res-0603-100K") (field (name "PUBLISHER") "Altium Limited"))
      (libsource (lib "RUMBA_v2") (part "Res-0603-100K"))
    )
    (comp (ref "R29")
      (value "10K")
      (footprint "RES 1608-0603")
      (description "Resistor")
      (fields (field (name "Comment") "Res-0603-10K") (field (name "PUBLISHER") "Altium Limited"))
      (libsource (lib "RUMBA_v2") (part "Res-0603-10K"))
    )
    (comp (ref "R30")
      (value "100K")
      (footprint "RES 1608-0603")
      (description "Resistor")
      (fields (field (name "Comment") "Res-0603-100K") (field (name "PUBLISHER") "Altium Limited"))
      (libsource (lib "RUMBA_v2") (part "Res-0603-100K"))
    )
    (comp (ref "R31")
      (value "22R")
      (footprint "RES 1608-0603")
      (description "Resistor")
      (fields (field (name "Comment") "Res-0603-22R") (field (name "PUBLISHER") "Altium Limited"))
      (libsource (lib "RUMBA_v2") (part "Res-0603-22R"))
    )
    (comp (ref "R32")
      (value "100K")
      (footprint "RES 1608-0603")
      (description "Resistor")
      (fields (field (name "Comment") "Res-0603-100K") (field (name "PUBLISHER") "Altium Limited"))
      (libsource (lib "RUMBA_v2") (part "Res-0603-100K"))
    )
    (comp (ref "R33")
      (value "1K")
      (footprint "RES 1608-0603")
      (description "Resistor")
      (fields (field (name "Comment") "Res-0603-1K") (field (name "PUBLISHER") "Altium Limited"))
      (libsource (lib "RUMBA_v2") (part "Res-0603-1K"))
    )
    (comp (ref "R34")
      (value "22R")
      (footprint "RES 1608-0603")
      (description "Resistor")
      (fields (field (name "Comment") "Res-0603-22R") (field (name "PUBLISHER") "Altium Limited"))
      (libsource (lib "RUMBA_v2") (part "Res-0603-22R"))
    )
    (comp (ref "R35")
      (value "100K")
      (footprint "RES 1608-0603")
      (description "Resistor")
      (fields (field (name "Comment") "Res-0603-100K") (field (name "PUBLISHER") "Altium Limited"))
      (libsource (lib "RUMBA_v2") (part "Res-0603-100K"))
    )
    (comp (ref "R36")
      (value "1K")
      (footprint "RES 1608-0603")
      (description "Resistor")
      (fields (field (name "Comment") "Res-0603-1K") (field (name "PUBLISHER") "Altium Limited"))
      (libsource (lib "RUMBA_v2") (part "Res-0603-1K"))
    )
    (comp (ref "R37")
      (value "22R")
      (footprint "RES 1608-0603")
      (description "Resistor")
      (fields (field (name "Comment") "Res-0603-22R") (field (name "PUBLISHER") "Altium Limited"))
      (libsource (lib "RUMBA_v2") (part "Res-0603-22R"))
    )
    (comp (ref "R38")
      (value "100K")
      (footprint "RES 1608-0603")
      (description "Resistor")
      (fields (field (name "Comment") "Res-0603-100K") (field (name "PUBLISHER") "Altium Limited"))
      (libsource (lib "RUMBA_v2") (part "Res-0603-100K"))
    )
    (comp (ref "R39")
      (value "1K")
      (footprint "RES 1608-0603")
      (description "Resistor")
      (fields (field (name "Comment") "Res-0603-1K") (field (name "PUBLISHER") "Altium Limited"))
      (libsource (lib "RUMBA_v2") (part "Res-0603-1K"))
    )
    (comp (ref "R40")
      (value "4.7K")
      (footprint "RES 1608-0603")
      (description "Resistor")
      (fields (field (name "Comment") "Res-0603-4K7") (field (name "PUBLISHER") "Altium Limited"))
      (libsource (lib "RUMBA_v2") (part "Res-0603-4K7"))
    )
    (comp (ref "R41")
      (value "4.7K")
      (footprint "RES 1608-0603")
      (description "Resistor")
      (fields (field (name "Comment") "Res-0603-4K7") (field (name "PUBLISHER") "Altium Limited"))
      (libsource (lib "RUMBA_v2") (part "Res-0603-4K7"))
    )
    (comp (ref "R42")
      (value "4.7K")
      (footprint "RES 1608-0603")
      (description "Resistor")
      (fields (field (name "Comment") "Res-0603-4K7") (field (name "PUBLISHER") "Altium Limited"))
      (libsource (lib "RUMBA_v2") (part "Res-0603-4K7"))
    )
    (comp (ref "R43")
      (value "4.7K")
      (footprint "RES 1608-0603")
      (description "Resistor")
      (fields (field (name "Comment") "Res-0603-4K7") (field (name "PUBLISHER") "Altium Limited"))
      (libsource (lib "RUMBA_v2") (part "Res-0603-4K7"))
    )
    (comp (ref "R44")
      (value "100K")
      (footprint "RES 1608-0603")
      (description "Resistor")
      (fields (field (name "Comment") "Res-0603-100K") (field (name "PUBLISHER") "Altium Limited"))
      (libsource (lib "RUMBA_v2") (part "Res-0603-100K"))
    )
    (comp (ref "R45")
      (value "10K")
      (footprint "RES 1608-0603")
      (description "Resistor")
      (fields (field (name "Comment") "Res-0603-10K") (field (name "PUBLISHER") "Altium Limited"))
      (libsource (lib "RUMBA_v2") (part "Res-0603-10K"))
    )
    (comp (ref "R46")
      (value "22R")
      (footprint "RES 1608-0603")
      (description "Resistor")
      (fields (field (name "Comment") "Res-0603-22R") (field (name "PUBLISHER") "Altium Limited"))
      (libsource (lib "RUMBA_v2") (part "Res-0603-22R"))
    )
    (comp (ref "R47")
      (value "100K")
      (footprint "RES 1608-0603")
      (description "Resistor")
      (fields (field (name "Comment") "Res-0603-100K") (field (name "PUBLISHER") "Altium Limited"))
      (libsource (lib "RUMBA_v2") (part "Res-0603-100K"))
    )
    (comp (ref "R48")
      (value "22R")
      (footprint "RES 1608-0603")
      (description "Resistor")
      (fields (field (name "Comment") "Res-0603-22R") (field (name "PUBLISHER") "Altium Limited"))
      (libsource (lib "RUMBA_v2") (part "Res-0603-22R"))
    )
    (comp (ref "R49")
      (value "100K")
      (footprint "RES 1608-0603")
      (description "Resistor")
      (fields (field (name "Comment") "Res-0603-100K") (field (name "PUBLISHER") "Altium Limited"))
      (libsource (lib "RUMBA_v2") (part "Res-0603-100K"))
    )
    (comp (ref "R50")
      (value "1K")
      (footprint "RES 1608-0603")
      (description "Resistor")
      (fields (field (name "Comment") "Res-0603-1K") (field (name "PUBLISHER") "Altium Limited"))
      (libsource (lib "RUMBA_v2") (part "Res-0603-1K"))
    )
    (comp (ref "R51")
      (value "22R")
      (footprint "RES 1608-0603")
      (description "Resistor")
      (fields (field (name "Comment") "Res-0603-22R") (field (name "PUBLISHER") "Altium Limited"))
      (libsource (lib "RUMBA_v2") (part "Res-0603-22R"))
    )
    (comp (ref "R52")
      (value "100K")
      (footprint "RES 1608-0603")
      (description "Resistor")
      (fields (field (name "Comment") "Res-0603-100K") (field (name "PUBLISHER") "Altium Limited"))
      (libsource (lib "RUMBA_v2") (part "Res-0603-100K"))
    )
    (comp (ref "R53")
      (value "1K")
      (footprint "RES 1608-0603")
      (description "Resistor")
      (fields (field (name "Comment") "Res-0603-1K") (field (name "PUBLISHER") "Altium Limited"))
      (libsource (lib "RUMBA_v2") (part "Res-0603-1K"))
    )
    (comp (ref "R54")
      (value "4.7K")
      (footprint "RES 1608-0603")
      (description "Resistor")
      (fields (field (name "Comment") "Res-0603-4K7") (field (name "PUBLISHER") "Altium Limited"))
      (libsource (lib "RUMBA_v2") (part "Res-0603-4K7"))
    )
    (comp (ref "R55")
      (value "1K")
      (footprint "RES 1608-0603")
      (description "Resistor")
      (fields (field (name "Comment") "Res-0603-1K") (field (name "PUBLISHER") "Altium Limited"))
      (libsource (lib "RUMBA_v2") (part "Res-0603-1K"))
    )
    (comp (ref "R56")
      (value "140K")
      (footprint "RES 1608-0603")
      (description "Resistor")
      (fields (field (name "Comment") "Res-0603-140K") (field (name "PUBLISHER") "Altium Limited"))
      (libsource (lib "RUMBA_v2") (part "Res-0603-1K"))
    )
    (comp (ref "R57")
      (value "10K")
      (footprint "RES 1608-0603")
      (description "Resistor")
      (fields (field (name "Comment") "Res-0603-10K") (field (name "PUBLISHER") "Altium Limited"))
      (libsource (lib "RUMBA_v2") (part "Res-0603-10K"))
    )
    (comp (ref "R58")
      (value "1K")
      (footprint "RES 1608-0603")
      (description "Resistor")
      (fields (field (name "Comment") "Res-0603-1K") (field (name "PUBLISHER") "Altium Limited"))
      (libsource (lib "RUMBA_v2") (part "Res-0603-1K"))
    )
    (comp (ref "R59")
      (value "4.7K")
      (footprint "RES 1608-0603")
      (description "Resistor")
      (fields (field (name "Comment") "Res-0603-4K7") (field (name "PUBLISHER") "Altium Limited"))
      (libsource (lib "RUMBA_v2") (part "Res-0603-4K7"))
    )
    (comp (ref "Reset")
      (value "SW-PB")
      (footprint "SW-PB SMD 2pin")
      (description "SMD Tactile Switch")
      (libsource (lib "RUMBA_v2") (part "SW-PB"))
    )
    (comp (ref "RX")
      (value "YELLOW")
      (footprint "LED 1608-0603")
      (description "Hyper-Bright LED")
      (libsource (lib "picoprint_library") (part "LEDY  0603"))
    )
    (comp (ref "sc1") (value "Sraf") (footprint "Sraf 3mm - rupa 3.2") (libsource (lib "gc") (part "Sraf")))
    (comp (ref "sc2") (value "Sraf") (footprint "Sraf 3mm - rupa 3.2") (libsource (lib "gc") (part "Sraf")))
    (comp (ref "sc3") (value "Sraf") (footprint "Sraf 3mm - rupa 3.5") (libsource (lib "gc") (part "Sraf")))
    (comp (ref "sc4") (value "Sraf") (footprint "Sraf 3mm - rupa 3.5") (libsource (lib "gc") (part "Sraf")))
    (comp (ref "Thermistors")
      (value "Header 5X2")
      (footprint "HDR2X5")
      (description "Header, 5-Pin, Dual row")
      (fields (field (name "PUBLISHER") "Altium Limited"))
      (libsource (lib "") (part "Header 5X2_1"))
    )
    (comp (ref "TX")
      (value "YELLOW")
      (footprint "LED 1608-0603")
      (description "Hyper-Bright LED")
      (libsource (lib "picoprint_library") (part "LEDY  0603"))
    )
    (comp (ref "U1")
      (value "ATMEGA2560")
      (footprint "TQFP100N")
      (description "The high-performance, low-power Atmel 8-bit AVR RISC-based microcontroller")
      (fields (field (name "SUPPLIER PART NUMBER 1") "ATMEGA2560-16AU-ND"))
      (libsource (lib "RUMBA_v2") (part "ATMEGA2560"))
    )
    (comp (ref "U2")
      (value "ATMEGA16U2-MU")
      (footprint "32M1-A_N")
      (description "High Performance, Low Power USB2.0 AVR® 8-Bit Microcontroller")
      (libsource (lib "RUMBA_v2") (part "ATMEGA16U2-MU"))
    )
    (comp (ref "U3")
      (value "AOZ1282CI")
      (footprint "SOT23-6N")
      (libsource (lib "Schlib1") (part "Buck Regulator AOZ1282CI"))
    )
    (comp (ref "U4")
      (value "AOZ1284")
      (footprint "SOIC127P600X170_HS-9N")
      (libsource (lib "picoprint_library") (part "Regulator - AOZ1284 4A Buck Regulator"))
    )
    (comp (ref "U5")
      (value "USBLC6-4SC6")
      (footprint "SOT23-6N")
      (description "ESD Protection IC")
      (libsource (lib "picoprint_library") (part "USBLC6-4SC6 USB ESD Protection"))
    )
    (comp (ref "USB_AUX")
      (value "Header 5")
      (footprint "HDR1X5-HEADER")
      (description "Header, 5-Pin")
      (fields (field (name "PUBLISHER") "Altium Limited"))
      (libsource (lib "picoprint_library") (part "Header 5x1"))
    )
    (comp (ref "VFA0_sel")
      (value "Header 3")
      (footprint "HDR1X3")
      (description "Header, 3-Pin")
      (fields (field (name "PUBLISHER") "Altium Limited"))
      (libsource (lib "RUMBA_v2") (part "Header 3"))
    )
    (comp (ref "VFA1_sel")
      (value "Header 3")
      (footprint "HDR1X3")
      (description "Header, 3-Pin")
      (fields (field (name "PUBLISHER") "Altium Limited"))
      (libsource (lib "RUMBA_v2") (part "Header 3"))
    )
    (comp (ref "VHE2_sel")
      (value "Header 3")
      (footprint "HDR1X3")
      (description "Header, 3-Pin")
      (fields (field (name "PUBLISHER") "Altium Limited"))
      (libsource (lib "RUMBA_v2") (part "Header 3"))
    )
    (comp (ref "X")
      (value "A4988BREAKOUT")
      (footprint "A4988BREAKOUT")
      (libsource (lib "RUMBA_v2") (part "A4988BREAKOUT"))
    )
    (comp (ref "X+")
      (value "Header 3")
      (footprint "HDR1X3")
      (description "Header, 3-Pin")
      (fields (field (name "PUBLISHER") "Altium Limited"))
      (libsource (lib "RUMBA_v2") (part "Header 3"))
    )
    (comp (ref "X-")
      (value "Header 3")
      (footprint "HDR1X3")
      (description "Header, 3-Pin")
      (fields (field (name "PUBLISHER") "Altium Limited"))
      (libsource (lib "RUMBA_v2") (part "Header 3"))
    )
    (comp (ref "X_MOT")
      (value "ScrewTerminal-3.5mm-4Way")
      (footprint "TERM4 3.5mm")
      (description "Screw Terminal 3.5mm 4-Way")
      (fields (field (name "PUBLISHER") "Altium Limited"))
      (libsource (lib "RUMBA_v2") (part "ScrewTerminal-3.5mm-4Way"))
    )
    (comp (ref "X_MOT_A")
      (value "Header 4")
      (footprint "HDR1X4")
      (description "Header, 4-Pin")
      (fields (field (name "PUBLISHER") "Altium Limited"))
      (libsource (lib "RUMBA_v2") (part "Header 4_1"))
    )
    (comp (ref "X_MS")
      (value "SW DIP-3")
      (footprint "dipsw SO6")
      (description "DIP Switch")
      (fields (field (name "PUBLISHER") "Altium Limited"))
      (libsource (lib "RUMBA_v2") (part "SW DIP-3"))
    )
    (comp (ref "Y")
      (value "A4988BREAKOUT")
      (footprint "A4988BREAKOUT")
      (libsource (lib "RUMBA_v2") (part "A4988BREAKOUT"))
    )
    (comp (ref "Y+")
      (value "Header 3")
      (footprint "HDR1X3")
      (description "Header, 3-Pin")
      (fields (field (name "PUBLISHER") "Altium Limited"))
      (libsource (lib "RUMBA_v2") (part "Header 3"))
    )
    (comp (ref "Y-")
      (value "Header 3")
      (footprint "HDR1X3")
      (description "Header, 3-Pin")
      (fields (field (name "PUBLISHER") "Altium Limited"))
      (libsource (lib "RUMBA_v2") (part "Header 3"))
    )
    (comp (ref "Y1")
      (value "16MHz")
      (footprint "3525 SMD Crystal")
      (description "Crystal Oscillator")
      (fields
        (field (name "MANUFACTURER") "Generic Components")
        (field (name "PUBLISHER") "Altium Hobart Technology Centre")
      )
      (libsource (lib "RUMBA_v2") (part "XTAL_2"))
    )
    (comp (ref "Y2")
      (value "16MHz")
      (footprint "3525 SMD Crystal")
      (description "Crystal Oscillator")
      (fields
        (field (name "MANUFACTURER") "Generic Components")
        (field (name "PUBLISHER") "Altium Hobart Technology Centre")
      )
      (libsource (lib "RUMBA_v2") (part "XTAL_2"))
    )
    (comp (ref "Y_MOT")
      (value "ScrewTerminal-3.5mm-4Way")
      (footprint "TERM4 3.5mm")
      (description "Screw Terminal 3.5mm 4-Way")
      (fields (field (name "PUBLISHER") "Altium Limited"))
      (libsource (lib "RUMBA_v2") (part "ScrewTerminal-3.5mm-4Way"))
    )
    (comp (ref "Y_MOT_A")
      (value "Header 4")
      (footprint "HDR1X4")
      (description "Header, 4-Pin")
      (fields (field (name "PUBLISHER") "Altium Limited"))
      (libsource (lib "RUMBA_v2") (part "Header 4_1"))
    )
    (comp (ref "Y_MS")
      (value "SW DIP-3")
      (footprint "dipsw SO6")
      (description "DIP Switch")
      (fields (field (name "PUBLISHER") "Altium Limited"))
      (libsource (lib "RUMBA_v2") (part "SW DIP-3"))
    )
    (comp (ref "Z")
      (value "A4988BREAKOUT")
      (footprint "A4988BREAKOUT")
      (libsource (lib "RUMBA_v2") (part "A4988BREAKOUT"))
    )
    (comp (ref "Z+")
      (value "Header 3")
      (footprint "HDR1X3")
      (description "Header, 3-Pin")
      (fields (field (name "PUBLISHER") "Altium Limited"))
      (libsource (lib "RUMBA_v2") (part "Header 3"))
    )
    (comp (ref "Z-")
      (value "Header 3")
      (footprint "HDR1X3")
      (description "Header, 3-Pin")
      (fields (field (name "PUBLISHER") "Altium Limited"))
      (libsource (lib "RUMBA_v2") (part "Header 3"))
    )
    (comp (ref "Z_MOT")
      (value "ScrewTerminal-3.5mm-4Way")
      (footprint "TERM4 3.5mm")
      (description "Screw Terminal 3.5mm 4-Way")
      (fields (field (name "PUBLISHER") "Altium Limited"))
      (libsource (lib "RUMBA_v2") (part "ScrewTerminal-3.5mm-4Way"))
    )
    (comp (ref "Z_MOT_A")
      (value "Header 4")
      (footprint "HDR1X4")
      (description "Header, 4-Pin")
      (fields (field (name "PUBLISHER") "Altium Limited"))
      (libsource (lib "RUMBA_v2") (part "Header 4_1"))
    )
    (comp (ref "Z_MS")
      (value "SW DIP-3")
      (footprint "dipsw SO6")
      (description "DIP Switch")
      (fields (field (name "PUBLISHER") "Altium Limited"))
      (libsource (lib "RUMBA_v2") (part "SW DIP-3"))
    )
  )
  (nets
    (net (code "1") (name "+5V") (class "Default")
      (node (ref "5V") (pin "1") (pinfunction "1_1") (pintype "passive"))
      (node (ref "C13") (pin "2") (pinfunction "2_2") (pintype "passive"))
      (node (ref "C5") (pin "2") (pinfunction "2_2") (pintype "passive"))
      (node (ref "C6") (pin "2") (pinfunction "2_2") (pintype "passive"))
      (node (ref "C7") (pin "2") (pinfunction "2_2") (pintype "passive"))
      (node (ref "D2") (pin "K") (pinfunction "K_K") (pintype "passive"))
      (node (ref "D3") (pin "K") (pinfunction "K_K") (pintype "passive"))
      (node (ref "D4") (pin "3") (pinfunction "K_3") (pintype "passive"))
      (node (ref "ENC_1") (pin "4") (pinfunction "4_4") (pintype "passive"))
      (node (ref "ENC_2") (pin "4") (pinfunction "4_4") (pintype "passive"))
      (node (ref "ENC_3") (pin "4") (pinfunction "4_4") (pintype "passive"))
      (node (ref "ENC_4") (pin "4") (pinfunction "4_4") (pintype "passive"))
      (node (ref "EXP1") (pin "10") (pinfunction "10_10") (pintype "passive"))
      (node (ref "EXP3") (pin "2") (pinfunction "2_2") (pintype "passive"))
      (node (ref "ISP1") (pin "2") (pinfunction "2_2") (pintype "passive"))
      (node (ref "ISP2") (pin "2") (pinfunction "2_2") (pintype "passive"))
      (node (ref "JTAG") (pin "4") (pinfunction "4_4") (pintype "passive"))
      (node (ref "JTAG") (pin "7") (pinfunction "7_7") (pintype "passive"))
      (node (ref "R11") (pin "2") (pinfunction "2_2") (pintype "passive"))
      (node (ref "R12") (pin "2") (pinfunction "2_2") (pintype "passive"))
      (node (ref "R15") (pin "1") (pinfunction "1_1") (pintype "passive"))
      (node (ref "R16") (pin "1") (pinfunction "1_1") (pintype "passive"))
      (node (ref "R2") (pin "2") (pinfunction "2_2") (pintype "passive"))
      (node (ref "R3") (pin "2") (pinfunction "2_2") (pintype "passive"))
      (node (ref "R40") (pin "1") (pinfunction "1_1") (pintype "passive"))
      (node (ref "R41") (pin "1") (pinfunction "1_1") (pintype "passive"))
      (node (ref "R42") (pin "1") (pinfunction "1_1") (pintype "passive"))
      (node (ref "R43") (pin "1") (pinfunction "1_1") (pintype "passive"))
      (node (ref "R54") (pin "1") (pinfunction "1_1") (pintype "passive"))
      (node (ref "R58") (pin "2") (pinfunction "2_2") (pintype "passive"))
      (node (ref "U1") (pin "10") (pinfunction "VCC_10") (pintype "passive"))
      (node (ref "U1") (pin "100") (pinfunction "AVCC_100") (pintype "passive"))
      (node (ref "U1") (pin "31") (pinfunction "VCC_31") (pintype "passive"))
      (node (ref "U1") (pin "61") (pinfunction "VCC_61") (pintype "passive"))
      (node (ref "U1") (pin "80") (pinfunction "VCC_80") (pintype "passive"))
      (node (ref "U2") (pin "32") (pinfunction "AVCC_32") (pintype "passive"))
      (node (ref "U2") (pin "4") (pinfunction "VCC_4") (pintype "passive"))
      (node (ref "X+") (pin "3") (pinfunction "3_3") (pintype "passive"))
      (node (ref "X-") (pin "3") (pinfunction "3_3") (pintype "passive"))
      (node (ref "Y+") (pin "3") (pinfunction "3_3") (pintype "passive"))
      (node (ref "Y-") (pin "3") (pinfunction "3_3") (pintype "passive"))
      (node (ref "Z+") (pin "3") (pinfunction "3_3") (pintype "passive"))
      (node (ref "Z-") (pin "3") (pinfunction "3_3") (pintype "passive"))
    )
    (net (code "2") (name "+12V") (class "Default")
      (node (ref "12V") (pin "1") (pinfunction "1_1") (pintype "passive"))
      (node (ref "C32") (pin "1") (pinfunction "1_1") (pintype "passive"))
      (node (ref "EXP3") (pin "1") (pinfunction "1_1") (pintype "passive"))
      (node (ref "L4") (pin "2") (pinfunction "2_2") (pintype "passive"))
      (node (ref "R56") (pin "1") (pinfunction "1_1") (pintype "passive"))
      (node (ref "R59") (pin "2") (pinfunction "2_2") (pintype "passive"))
      (node (ref "VFA0_sel") (pin "3") (pinfunction "3_3") (pintype "passive"))
      (node (ref "VFA1_sel") (pin "3") (pinfunction "3_3") (pintype "passive"))
      (node (ref "VHE2_sel") (pin "3") (pinfunction "3_3") (pintype "passive"))
    )
    (net (code "3") (name "/A9") (class "Default")
      (node (ref "EXP3") (pin "7") (pinfunction "7_7") (pintype "passive"))
      (node (ref "U1") (pin "88") (pinfunction "PK1(ADC9/PCINT17)_88") (pintype "passive"))
    )
    (net (code "4") (name "/A10") (class "Default")
      (node (ref "EXP3") (pin "8") (pinfunction "8_8") (pintype "passive"))
      (node (ref "U1") (pin "87") (pinfunction "PK2(ADC10/PCINT18)_87") (pintype "passive"))
    )
    (net (code "5") (name "/AREF") (class "Default")
      (node (ref "C4") (pin "2") (pinfunction "2_2") (pintype "passive"))
      (node (ref "U1") (pin "98") (pinfunction "AREF_98") (pintype "passive"))
    )
    (net (code "6") (name "/BEEPER") (class "Default")
      (node (ref "EXP1") (pin "1") (pinfunction "1_1") (pintype "passive"))
      (node (ref "U1") (pin "40") (pinfunction "PL5(OC5C)_40") (pintype "passive"))
    )
    (net (code "7") (name "/BTN_EN1") (class "Default")
      (node (ref "EXP2") (pin "5") (pinfunction "5_5") (pintype "passive"))
      (node (ref "U1") (pin "25") (pinfunction "(OC1B/PCINT6)PB6_25") (pintype "passive"))
    )
    (net (code "8") (name "/BTN_EN2") (class "Default")
      (node (ref "EXP2") (pin "3") (pinfunction "3_3") (pintype "passive"))
      (node (ref "U1") (pin "24") (pinfunction "(OC1A/PCINT5)PB5_24") (pintype "passive"))
    )
    (net (code "9") (name "/BTN_ENC") (class "Default")
      (node (ref "EXP1") (pin "2") (pinfunction "2_2") (pintype "passive"))
      (node (ref "U1") (pin "41") (pinfunction "PL6_41") (pintype "passive"))
    )
    (net (code "10") (name "/DTR") (class "Default")
      (node (ref "C16") (pin "2") (pinfunction "2_2") (pintype "passive"))
      (node (ref "R14") (pin "1") (pinfunction "1_1") (pintype "passive"))
      (node (ref "U2") (pin "13") (pinfunction "(CTS/HWB/AIN6/TO/INT7)PD7_13") (pintype "passive"))
    )
    (net (code "11") (name "/E0-DIR") (class "Default")
      (node (ref "E0") (pin "8") (pinfunction "DIR_8") (pintype "passive"))
      (node (ref "U1") (pin "78") (pinfunction "(AD0)PA0_78") (pintype "passive"))
    )
    (net (code "12") (name "/E0-EN") (class "Default")
      (node (ref "E0") (pin "1") (pinfunction "~{ENA}_1") (pintype "passive"))
      (node (ref "R27") (pin "2") (pinfunction "2_2") (pintype "passive"))
      (node (ref "U1") (pin "76") (pinfunction "(AD2)PA2_76") (pintype "passive"))
    )
    (net (code "13") (name "/E0-STEP") (class "Default")
      (node (ref "E0") (pin "7") (pinfunction "STEP_7") (pintype "passive"))
      (node (ref "U1") (pin "77") (pinfunction "(AD1)PA1_77") (pintype "passive"))
    )
    (net (code "14") (name "/E1-DIR") (class "Default")
      (node (ref "E1") (pin "8") (pinfunction "DIR_8") (pintype "passive"))
      (node (ref "U1") (pin "75") (pinfunction "(AD3)PA3_75") (pintype "passive"))
    )
    (net (code "15") (name "/E1-EN") (class "Default")
      (node (ref "E1") (pin "1") (pinfunction "~{ENA}_1") (pintype "passive"))
      (node (ref "R29") (pin "2") (pinfunction "2_2") (pintype "passive"))
      (node (ref "U1") (pin "73") (pinfunction "(AD5)PA5_73") (pintype "passive"))
    )
    (net (code "16") (name "/E1-STEP") (class "Default")
      (node (ref "E1") (pin "7") (pinfunction "STEP_7") (pintype "passive"))
      (node (ref "U1") (pin "74") (pinfunction "(AD4)PA4_74") (pintype "passive"))
    )
    (net (code "17") (name "/E2-DIR") (class "Default")
      (node (ref "E2") (pin "8") (pinfunction "DIR_8") (pintype "passive"))
      (node (ref "U1") (pin "72") (pinfunction "(AD6)PA6_72") (pintype "passive"))
    )
    (net (code "18") (name "/E2-EN") (class "Default")
      (node (ref "E2") (pin "1") (pinfunction "~{ENA}_1") (pintype "passive"))
      (node (ref "R45") (pin "2") (pinfunction "2_2") (pintype "passive"))
      (node (ref "U1") (pin "70") (pinfunction "(ALE)PG2_70") (pintype "passive"))
    )
    (net (code "19") (name "/E2-STEP") (class "Default")
      (node (ref "E2") (pin "7") (pinfunction "STEP_7") (pintype "passive"))
      (node (ref "U1") (pin "71") (pinfunction "(AD7)PA7_71") (pintype "passive"))
    )
    (net (code "20") (name "/FAN_0") (class "Default")
      (node (ref "R46") (pin "1") (pinfunction "1_1") (pintype "passive"))
      (node (ref "R47") (pin "1") (pinfunction "1_1") (pintype "passive"))
      (node (ref "R55") (pin "2") (pinfunction "2_2") (pintype "passive"))
      (node (ref "U1") (pin "17") (pinfunction "PH5(OC4C)_17") (pintype "passive"))
    )
    (net (code "21") (name "/FAN_1") (class "Default")
      (node (ref "R51") (pin "1") (pinfunction "1_1") (pintype "passive"))
      (node (ref "R52") (pin "1") (pinfunction "1_1") (pintype "passive"))
      (node (ref "R53") (pin "2") (pinfunction "2_2") (pintype "passive"))
      (node (ref "U1") (pin "16") (pinfunction "PH4(OC4B)_16") (pintype "passive"))
    )
    (net (code "22") (name "/FB1") (class "Default")
      (node (ref "R5") (pin "1") (pinfunction "1_1") (pintype "passive"))
      (node (ref "R6") (pin "2") (pinfunction "2_2") (pintype "passive"))
      (node (ref "U3") (pin "3") (pinfunction "FB_3") (pintype "passive"))
    )
    (net (code "23") (name "/FB2") (class "Default")
      (node (ref "R56") (pin "2") (pinfunction "2_2") (pintype "passive"))
      (node (ref "R57") (pin "2") (pinfunction "2_2") (pintype "passive"))
      (node (ref "U4") (pin "6") (pinfunction "FB_6") (pintype "passive"))
    )
    (net (code "24") (name "/HB") (class "Default")
      (node (ref "R31") (pin "1") (pinfunction "1_1") (pintype "passive"))
      (node (ref "R32") (pin "1") (pinfunction "1_1") (pintype "passive"))
      (node (ref "R33") (pin "2") (pinfunction "2_2") (pintype "passive"))
      (node (ref "U1") (pin "18") (pinfunction "PH6(OC2B)_18") (pintype "passive"))
    )
    (net (code "25") (name "/HE_0") (class "Default")
      (node (ref "R34") (pin "1") (pinfunction "1_1") (pintype "passive"))
      (node (ref "R35") (pin "1") (pinfunction "1_1") (pintype "passive"))
      (node (ref "R36") (pin "2") (pinfunction "2_2") (pintype "passive"))
      (node (ref "U1") (pin "6") (pinfunction "(OC3B/INT4)PE4_6") (pintype "passive"))
    )
    (net (code "26") (name "/HE_1") (class "Default")
      (node (ref "R37") (pin "1") (pinfunction "1_1") (pintype "passive"))
      (node (ref "R38") (pin "1") (pinfunction "1_1") (pintype "passive"))
      (node (ref "R39") (pin "2") (pinfunction "2_2") (pintype "passive"))
      (node (ref "U1") (pin "7") (pinfunction "(OC3C/INT5)PE5_7") (pintype "passive"))
    )
    (net (code "27") (name "/HE_2") (class "Default")
      (node (ref "R48") (pin "1") (pinfunction "1_1") (pintype "passive"))
      (node (ref "R49") (pin "1") (pinfunction "1_1") (pintype "passive"))
      (node (ref "R50") (pin "2") (pinfunction "2_2") (pintype "passive"))
      (node (ref "U1") (pin "15") (pinfunction "PH3(OC4A)_15") (pintype "passive"))
    )
    (net (code "28") (name "/J_TCK") (class "Default")
      (node (ref "JTAG") (pin "1") (pinfunction "1_1") (pintype "passive"))
      (node (ref "U1") (pin "93") (pinfunction "(ADC4/TCK)PF4_93") (pintype "passive"))
    )
    (net (code "29") (name "/J_TDI") (class "Default")
      (node (ref "JTAG") (pin "9") (pinfunction "9_9") (pintype "passive"))
      (node (ref "U1") (pin "90") (pinfunction "(ADC7/TDI)PF7_90") (pintype "passive"))
    )
    (net (code "30") (name "/J_TDO") (class "Default")
      (node (ref "JTAG") (pin "3") (pinfunction "3_3") (pintype "passive"))
      (node (ref "U1") (pin "91") (pinfunction "(ADC6/TDO)PF6_91") (pintype "passive"))
    )
    (net (code "31") (name "/J_TMS") (class "Default")
      (node (ref "JTAG") (pin "5") (pinfunction "5_5") (pintype "passive"))
      (node (ref "U1") (pin "92") (pinfunction "(ADC5/TMS)PF5_92") (pintype "passive"))
    )
    (net (code "32") (name "/KILL") (class "Default")
      (node (ref "EXP2") (pin "10") (pinfunction "10_10") (pintype "passive"))
      (node (ref "U1") (pin "38") (pinfunction "PL3(OC5A)_38") (pintype "passive"))
    )
    (net (code "33") (name "/LCD_D4") (class "Default")
      (node (ref "EXP1") (pin "5") (pinfunction "5_5") (pintype "passive"))
      (node (ref "U1") (pin "46") (pinfunction "(TXD1/INT3)PD3_46") (pintype "passive"))
    )
    (net (code "34") (name "/LCD_D5") (class "Default")
      (node (ref "EXP1") (pin "6") (pinfunction "6_6") (pintype "passive"))
      (node (ref "U1") (pin "50") (pinfunction "(T0)PD7_50") (pintype "passive"))
    )
    (net (code "35") (name "/LCD_D6") (class "Default")
      (node (ref "EXP1") (pin "7") (pinfunction "7_7") (pintype "passive"))
      (node (ref "U1") (pin "51") (pinfunction "(WR)PG0_51") (pintype "passive"))
    )
    (net (code "36") (name "/LCD_D7") (class "Default")
      (node (ref "EXP1") (pin "8") (pinfunction "8_8") (pintype "passive"))
      (node (ref "U1") (pin "52") (pinfunction "(RD)PG1_52") (pintype "passive"))
    )
    (net (code "37") (name "/LCD_ENA") (class "Default")
      (node (ref "EXP1") (pin "3") (pinfunction "3_3") (pintype "passive"))
      (node (ref "U1") (pin "42") (pinfunction "PL7_42") (pintype "passive"))
    )
    (net (code "38") (name "/LCD_RS") (class "Default")
      (node (ref "EXP1") (pin "4") (pinfunction "4_4") (pintype "passive"))
      (node (ref "U1") (pin "45") (pinfunction "(RXD1/INT2)PD2_45") (pintype "passive"))
    )
    (net (code "39") (name "/LED") (class "Default")
      (node (ref "R13") (pin "2") (pinfunction "2_2") (pintype "passive"))
      (node (ref "U1") (pin "26") (pinfunction "(OC0A/OC1C/PCINT7)PB7_26") (pintype "passive"))
    )
    (net (code "40") (name "/MISO2") (class "Default")
      (node (ref "ISP2") (pin "1") (pinfunction "1_1") (pintype "passive"))
      (node (ref "U2") (pin "17") (pinfunction "(PD0/MISO/PCINT3)PB3_17") (pintype "passive"))
    )
    (net (code "41") (name "/MOSI2") (class "Default")
      (node (ref "ISP2") (pin "4") (pinfunction "4_4") (pintype "passive"))
      (node (ref "U2") (pin "16") (pinfunction "(PDI/MOSI/PCINT2)PB2_16") (pintype "passive"))
    )
    (net (code "42") (name "/PB1_(SCK)") (class "Default")
      (node (ref "EXP2") (pin "2") (pinfunction "2_2") (pintype "passive"))
      (node (ref "ISP1") (pin "3") (pinfunction "3_3") (pintype "passive"))
      (node (ref "U1") (pin "20") (pinfunction "(SCK/PCINT1)PB1_20") (pintype "passive"))
    )
    (net (code "43") (name "/PB2_(MOSI)") (class "Default")
      (node (ref "EXP2") (pin "6") (pinfunction "6_6") (pintype "passive"))
      (node (ref "ISP1") (pin "4") (pinfunction "4_4") (pintype "passive"))
      (node (ref "U1") (pin "21") (pinfunction "(MOSI/PCINT2)PB2_21") (pintype "passive"))
    )
    (net (code "44") (name "/PB3_(MISO)") (class "Default")
      (node (ref "EXP2") (pin "1") (pinfunction "1_1") (pintype "passive"))
      (node (ref "ISP1") (pin "1") (pinfunction "1_1") (pintype "passive"))
      (node (ref "U1") (pin "22") (pinfunction "(MISO/PCINT3)PB3_22") (pintype "passive"))
    )
    (net (code "45") (name "/PC6") (class "Default")
      (node (ref "EXP3") (pin "14") (pinfunction "14_14") (pintype "passive"))
      (node (ref "U1") (pin "59") (pinfunction "(A14)PC6_59") (pintype "passive"))
    )
    (net (code "46") (name "/PC7") (class "Default")
      (node (ref "EXP3") (pin "13") (pinfunction "13_13") (pintype "passive"))
      (node (ref "U1") (pin "60") (pinfunction "(A15)PC7_60") (pintype "passive"))
    )
    (net (code "47") (name "/PJ0") (class "Default")
      (node (ref "EXP3") (pin "12") (pinfunction "12_12") (pintype "passive"))
      (node (ref "U1") (pin "63") (pinfunction "PJ0(RXD3/PCINT9)_63") (pintype "passive"))
    )
    (net (code "48") (name "/PJ1") (class "Default")
      (node (ref "EXP3") (pin "11") (pinfunction "11_11") (pintype "passive"))
      (node (ref "U1") (pin "64") (pinfunction "PJ1(TXD3/PCINT10)_64") (pintype "passive"))
    )
    (net (code "49") (name "/PS_ON") (class "Default")
      (node (ref "PS_ON") (pin "1") (pinfunction "1_1") (pintype "passive"))
      (node (ref "U1") (pin "39") (pinfunction "PL4(OC5B)_39") (pintype "passive"))
    )
    (net (code "50") (name "/PWM_1") (class "Default")
      (node (ref "EXP3") (pin "5") (pinfunction "5_5") (pintype "passive"))
      (node (ref "U1") (pin "1") (pinfunction "(OC0B)PG5_1") (pintype "passive"))
    )
    (net (code "51") (name "/PWM_2") (class "Default")
      (node (ref "EXP3") (pin "6") (pinfunction "6_6") (pintype "passive"))
      (node (ref "U1") (pin "5") (pinfunction "(OC3A/AIN1)PE3_5") (pintype "passive"))
    )
    (net (code "52") (name "/RESET") (class "Default")
      (node (ref "C16") (pin "1") (pinfunction "1_1") (pintype "passive"))
      (node (ref "C8") (pin "2") (pinfunction "2_2") (pintype "passive"))
      (node (ref "D2") (pin "A") (pinfunction "A_A") (pintype "passive"))
      (node (ref "EXP2") (pin "8") (pinfunction "8_8") (pintype "passive"))
      (node (ref "ISP1") (pin "5") (pinfunction "5_5") (pintype "passive"))
      (node (ref "JTAG") (pin "6") (pinfunction "6_6") (pintype "passive"))
      (node (ref "R11") (pin "1") (pinfunction "1_1") (pintype "passive"))
      (node (ref "Reset") (pin "2") (pintype "passive"))
      (node (ref "U1") (pin "30") (pinfunction "~{RESET}_30") (pintype "passive"))
    )
    (net (code "53") (name "/RESET2") (class "Default")
      (node (ref "D3") (pin "A") (pinfunction "A_A") (pintype "passive"))
      (node (ref "ISP2") (pin "5") (pinfunction "5_5") (pintype "passive"))
      (node (ref "R12") (pin "1") (pinfunction "1_1") (pintype "passive"))
      (node (ref "U2") (pin "24") (pinfunction "RESET(PC1/DW)_24") (pintype "passive"))
    )
    (net (code "54") (name "/SCK2") (class "Default")
      (node (ref "ISP2") (pin "3") (pinfunction "3_3") (pintype "passive"))
      (node (ref "U2") (pin "15") (pinfunction "(SCLK/PCINT1)PB1_15") (pintype "passive"))
    )
    (net (code "55") (name "/SCL") (class "Default")
      (node (ref "ENC_1") (pin "1") (pinfunction "1_1") (pintype "passive"))
      (node (ref "ENC_2") (pin "1") (pinfunction "1_1") (pintype "passive"))
      (node (ref "ENC_3") (pin "1") (pinfunction "1_1") (pintype "passive"))
      (node (ref "ENC_4") (pin "1") (pinfunction "1_1") (pintype "passive"))
      (node (ref "EXP3") (pin "9") (pinfunction "9_9") (pintype "passive"))
      (node (ref "R3") (pin "1") (pinfunction "1_1") (pintype "passive"))
      (node (ref "U1") (pin "43") (pinfunction "(SCL/INT0)PD0_43") (pintype "passive"))
    )
    (net (code "56") (name "/SDA") (class "Default")
      (node (ref "ENC_1") (pin "2") (pinfunction "2_2") (pintype "passive"))
      (node (ref "ENC_2") (pin "2") (pinfunction "2_2") (pintype "passive"))
      (node (ref "ENC_3") (pin "2") (pinfunction "2_2") (pintype "passive"))
      (node (ref "ENC_4") (pin "2") (pinfunction "2_2") (pintype "passive"))
      (node (ref "EXP3") (pin "10") (pinfunction "10_10") (pintype "passive"))
      (node (ref "R2") (pin "1") (pinfunction "1_1") (pintype "passive"))
      (node (ref "U1") (pin "44") (pinfunction "(SDA/INT1)PD1_44") (pintype "passive"))
    )
    (net (code "57") (name "/SD_CSEL") (class "Default")
      (node (ref "EXP2") (pin "4") (pinfunction "4_4") (pintype "passive"))
      (node (ref "U1") (pin "19") (pinfunction "(SS/PCINT0)PB0_19") (pintype "passive"))
    )
    (net (code "58") (name "/SD_DET") (class "Default")
      (node (ref "EXP2") (pin "7") (pinfunction "7_7") (pintype "passive"))
      (node (ref "U1") (pin "35") (pinfunction "PL0(ICP4)_35") (pintype "passive"))
    )
    (net (code "59") (name "/THERM0") (class "Default")
      (node (ref "C29") (pin "1") (pintype "passive"))
      (node (ref "R43") (pin "2") (pinfunction "2_2") (pintype "passive"))
      (node (ref "Thermistors") (pin "2") (pinfunction "2_2") (pintype "passive"))
      (node (ref "U1") (pin "82") (pinfunction "PK7(ADC15/PCINT23)_82") (pintype "passive"))
    )
    (net (code "60") (name "/THERM1") (class "Default")
      (node (ref "C28") (pin "1") (pintype "passive"))
      (node (ref "R42") (pin "2") (pinfunction "2_2") (pintype "passive"))
      (node (ref "Thermistors") (pin "4") (pinfunction "4_4") (pintype "passive"))
      (node (ref "U1") (pin "83") (pinfunction "PK6(ADC14/PCINT22)_83") (pintype "passive"))
    )
    (net (code "61") (name "/THERM2") (class "Default")
      (node (ref "C27") (pin "1") (pintype "passive"))
      (node (ref "R41") (pin "2") (pinfunction "2_2") (pintype "passive"))
      (node (ref "Thermistors") (pin "6") (pinfunction "6_6") (pintype "passive"))
      (node (ref "U1") (pin "84") (pinfunction "PK5(ADC13/PCINT21)_84") (pintype "passive"))
    )
    (net (code "62") (name "/THERM3") (class "Default")
      (node (ref "C26") (pin "1") (pintype "passive"))
      (node (ref "R40") (pin "2") (pinfunction "2_2") (pintype "passive"))
      (node (ref "Thermistors") (pin "8") (pinfunction "8_8") (pintype "passive"))
      (node (ref "U1") (pin "85") (pinfunction "PK4(ADC12/PCINT20)_85") (pintype "passive"))
    )
    (net (code "63") (name "/THERM4") (class "Default")
      (node (ref "C9") (pin "1") (pintype "passive"))
      (node (ref "R54") (pin "2") (pinfunction "2_2") (pintype "passive"))
      (node (ref "Thermistors") (pin "10") (pinfunction "10_10") (pintype "passive"))
      (node (ref "U1") (pin "86") (pinfunction "PK3(ADC11/PCINT19)_86") (pintype "passive"))
    )
    (net (code "64") (name "/USB RXD") (class "Default")
      (node (ref "R18") (pin "2") (pinfunction "2_2") (pintype "passive"))
      (node (ref "U1") (pin "2") (pinfunction "(RXD0/PCIN8)PE0_2") (pintype "passive"))
    )
    (net (code "65") (name "/USB_TXD") (class "Default")
      (node (ref "R17") (pin "2") (pinfunction "2_2") (pintype "passive"))
      (node (ref "U1") (pin "3") (pinfunction "(TXD0)PE1_3") (pintype "passive"))
    )
    (net (code "66") (name "/USB_XCK") (class "Default")
      (node (ref "U1") (pin "4") (pinfunction "(XCK0/AIN0)PE2_4") (pintype "passive"))
    )
    (net (code "67") (name "/X-DIR") (class "Default")
      (node (ref "U1") (pin "13") (pinfunction "PH1(TXD2)_13") (pintype "passive"))
      (node (ref "X") (pin "8") (pinfunction "DIR_8") (pintype "passive"))
    )
    (net (code "68") (name "/X-EN") (class "Default")
      (node (ref "R21") (pin "2") (pinfunction "2_2") (pintype "passive"))
      (node (ref "U1") (pin "36") (pinfunction "PL1(ICP5)_36") (pintype "passive"))
      (node (ref "X") (pin "1") (pinfunction "~{ENA}_1") (pintype "passive"))
    )
    (net (code "69") (name "/X-MAX") (class "Default")
      (node (ref "U1") (pin "54") (pinfunction "(A9)PC1_54") (pintype "passive"))
      (node (ref "X+") (pin "1") (pinfunction "1_1") (pintype "passive"))
    )
    (net (code "70") (name "/X-MIN") (class "Default")
      (node (ref "U1") (pin "53") (pinfunction "(A8)PC0_53") (pintype "passive"))
      (node (ref "X-") (pin "1") (pinfunction "1_1") (pintype "passive"))
    )
    (net (code "71") (name "/X-STEP") (class "Default")
      (node (ref "U1") (pin "12") (pinfunction "PH0(RXD2)_12") (pintype "passive"))
      (node (ref "X") (pin "7") (pinfunction "STEP_7") (pintype "passive"))
    )
    (net (code "72") (name "/Y-DIR") (class "Default")
      (node (ref "U1") (pin "37") (pinfunction "PL2(T5)_37") (pintype "passive"))
      (node (ref "Y") (pin "8") (pinfunction "DIR_8") (pintype "passive"))
    )
    (net (code "73") (name "/Y-EN") (class "Default")
      (node (ref "R23") (pin "2") (pinfunction "2_2") (pintype "passive"))
      (node (ref "U1") (pin "96") (pinfunction "(ADC1)PF1_96") (pintype "passive"))
      (node (ref "Y") (pin "1") (pinfunction "~{ENA}_1") (pintype "passive"))
    )
    (net (code "74") (name "/Y-MAX") (class "Default")
      (node (ref "U1") (pin "56") (pinfunction "(A11)PC3_56") (pintype "passive"))
      (node (ref "Y+") (pin "1") (pinfunction "1_1") (pintype "passive"))
    )
    (net (code "75") (name "/Y-MIN") (class "Default")
      (node (ref "U1") (pin "55") (pinfunction "(A10)PC2_55") (pintype "passive"))
      (node (ref "Y-") (pin "1") (pinfunction "1_1") (pintype "passive"))
    )
    (net (code "76") (name "/Y-STEP") (class "Default")
      (node (ref "U1") (pin "97") (pinfunction "(ADC0)PF0_97") (pintype "passive"))
      (node (ref "Y") (pin "7") (pinfunction "STEP_7") (pintype "passive"))
    )
    (net (code "77") (name "/Z-DIR") (class "Default")
      (node (ref "U1") (pin "95") (pinfunction "(ADC2)PF2_95") (pintype "passive"))
      (node (ref "Z") (pin "8") (pinfunction "DIR_8") (pintype "passive"))
    )
    (net (code "78") (name "/Z-EN") (class "Default")
      (node (ref "R25") (pin "2") (pinfunction "2_2") (pintype "passive"))
      (node (ref "U1") (pin "89") (pinfunction "PK0(ADC8/PCINT16)_89") (pintype "passive"))
      (node (ref "Z") (pin "1") (pinfunction "~{ENA}_1") (pintype "passive"))
    )
    (net (code "79") (name "/Z-MAX") (class "Default")
      (node (ref "U1") (pin "58") (pinfunction "(A13)PC5_58") (pintype "passive"))
      (node (ref "Z+") (pin "1") (pinfunction "1_1") (pintype "passive"))
    )
    (net (code "80") (name "/Z-MIN") (class "Default")
      (node (ref "U1") (pin "57") (pinfunction "(A12)PC4_57") (pintype "passive"))
      (node (ref "Z-") (pin "1") (pinfunction "1_1") (pintype "passive"))
    )
    (net (code "81") (name "/Z-STEP") (class "Default")
      (node (ref "U1") (pin "94") (pinfunction "(ADC3)PF3_94") (pintype "passive"))
      (node (ref "Z") (pin "7") (pinfunction "STEP_7") (pintype "passive"))
    )
    (net (code "82") (name "5V_DCDC") (class "Default")
      (node (ref "C2") (pin "1") (pinfunction "1_1") (pintype "passive"))
      (node (ref "D4") (pin "2") (pinfunction "A_2") (pintype "passive"))
      (node (ref "E0") (pin "10") (pinfunction "VDD_10") (pintype "passive"))
      (node (ref "E0_MS") (pin "1") (pinfunction "A1_1") (pintype "passive"))
      (node (ref "E0_MS") (pin "2") (pinfunction "A2_2") (pintype "passive"))
      (node (ref "E0_MS") (pin "3") (pinfunction "A3_3") (pintype "passive"))
      (node (ref "E1") (pin "10") (pinfunction "VDD_10") (pintype "passive"))
      (node (ref "E1_MS") (pin "1") (pinfunction "A1_1") (pintype "passive"))
      (node (ref "E1_MS") (pin "2") (pinfunction "A2_2") (pintype "passive"))
      (node (ref "E1_MS") (pin "3") (pinfunction "A3_3") (pintype "passive"))
      (node (ref "E2") (pin "10") (pinfunction "VDD_10") (pintype "passive"))
      (node (ref "E2_MS") (pin "1") (pinfunction "A1_1") (pintype "passive"))
      (node (ref "E2_MS") (pin "2") (pinfunction "A2_2") (pintype "passive"))
      (node (ref "E2_MS") (pin "3") (pinfunction "A3_3") (pintype "passive"))
      (node (ref "L3") (pin "2") (pinfunction "2_2") (pintype "passive"))
      (node (ref "R20") (pin "2") (pinfunction "2_2") (pintype "passive"))
      (node (ref "R21") (pin "1") (pinfunction "1_1") (pintype "passive"))
      (node (ref "R23") (pin "1") (pinfunction "1_1") (pintype "passive"))
      (node (ref "R25") (pin "1") (pinfunction "1_1") (pintype "passive"))
      (node (ref "R27") (pin "1") (pinfunction "1_1") (pintype "passive"))
      (node (ref "R29") (pin "1") (pinfunction "1_1") (pintype "passive"))
      (node (ref "R45") (pin "1") (pinfunction "1_1") (pintype "passive"))
      (node (ref "R5") (pin "2") (pinfunction "2_2") (pintype "passive"))
      (node (ref "U4") (pin "8") (pinfunction "EN_8") (pintype "passive"))
      (node (ref "X") (pin "10") (pinfunction "VDD_10") (pintype "passive"))
      (node (ref "X_MS") (pin "1") (pinfunction "A1_1") (pintype "passive"))
      (node (ref "X_MS") (pin "2") (pinfunction "A2_2") (pintype "passive"))
      (node (ref "X_MS") (pin "3") (pinfunction "A3_3") (pintype "passive"))
      (node (ref "Y") (pin "10") (pinfunction "VDD_10") (pintype "passive"))
      (node (ref "Y_MS") (pin "1") (pinfunction "A1_1") (pintype "passive"))
      (node (ref "Y_MS") (pin "2") (pinfunction "A2_2") (pintype "passive"))
      (node (ref "Y_MS") (pin "3") (pinfunction "A3_3") (pintype "passive"))
      (node (ref "Z") (pin "10") (pinfunction "VDD_10") (pintype "passive"))
      (node (ref "Z_MS") (pin "1") (pinfunction "A1_1") (pintype "passive"))
      (node (ref "Z_MS") (pin "2") (pinfunction "A2_2") (pintype "passive"))
      (node (ref "Z_MS") (pin "3") (pinfunction "A3_3") (pintype "passive"))
    )
    (net (code "83") (name "GND") (class "Default")
      (node (ref "12V") (pin "2") (pinfunction "2_2") (pintype "passive"))
      (node (ref "5V") (pin "2") (pinfunction "2_2") (pintype "passive"))
      (node (ref "C1") (pin "2") (pinfunction "2_2") (pintype "passive"))
      (node (ref "C11") (pin "1") (pinfunction "1_1") (pintype "passive"))
      (node (ref "C12") (pin "2") (pintype "passive"))
      (node (ref "C13") (pin "1") (pinfunction "1_1") (pintype "passive"))
      (node (ref "C14") (pin "1") (pinfunction "1_1") (pintype "passive"))
      (node (ref "C15") (pin "1") (pinfunction "1_1") (pintype "passive"))
      (node (ref "C17") (pin "1") (pinfunction "1_1") (pintype "passive"))
      (node (ref "C19") (pin "1") (pinfunction "1_1") (pintype "passive"))
      (node (ref "C2") (pin "2") (pinfunction "2_2") (pintype "passive"))
      (node (ref "C20") (pin "1") (pinfunction "1_1") (pintype "passive"))
      (node (ref "C21") (pin "2") (pinfunction "2_2") (pintype "passive"))
      (node (ref "C22") (pin "2") (pinfunction "2_2") (pintype "passive"))
      (node (ref "C23") (pin "2") (pinfunction "2_2") (pintype "passive"))
      (node (ref "C24") (pin "2") (pinfunction "2_2") (pintype "passive"))
      (node (ref "C25") (pin "2") (pinfunction "2_2") (pintype "passive"))
      (node (ref "C26") (pin "2") (pintype "passive"))
      (node (ref "C27") (pin "2") (pintype "passive"))
      (node (ref "C28") (pin "2") (pintype "passive"))
      (node (ref "C29") (pin "2") (pintype "passive"))
      (node (ref "C3") (pin "2") (pintype "passive"))
      (node (ref "C30") (pin "2") (pinfunction "2_2") (pintype "passive"))
      (node (ref "C31") (pin "2") (pinfunction "2_2") (pintype "passive"))
      (node (ref "C32") (pin "2") (pinfunction "2_2") (pintype "passive"))
      (node (ref "C34") (pin "1") (pinfunction "1_1") (pintype "passive"))
      (node (ref "C4") (pin "1") (pinfunction "1_1") (pintype "passive"))
      (node (ref "C5") (pin "1") (pinfunction "1_1") (pintype "passive"))
      (node (ref "C6") (pin "1") (pinfunction "1_1") (pintype "passive"))
      (node (ref "C7") (pin "1") (pinfunction "1_1") (pintype "passive"))
      (node (ref "C8") (pin "1") (pinfunction "1_1") (pintype "passive"))
      (node (ref "C9") (pin "2") (pintype "passive"))
      (node (ref "D5") (pin "A") (pinfunction "A_A") (pintype "passive"))
      (node (ref "D6") (pin "A") (pinfunction "A_A") (pintype "passive"))
      (node (ref "D7") (pin "A") (pinfunction "A_A") (pintype "passive"))
      (node (ref "D8") (pin "A") (pinfunction "A_A") (pintype "passive"))
      (node (ref "E0") (pin "15") (pinfunction "GND_15") (pintype "passive"))
      (node (ref "E0") (pin "9") (pinfunction "GND_9") (pintype "passive"))
      (node (ref "E1") (pin "15") (pinfunction "GND_15") (pintype "passive"))
      (node (ref "E1") (pin "9") (pinfunction "GND_9") (pintype "passive"))
      (node (ref "E2") (pin "15") (pinfunction "GND_15") (pintype "passive"))
      (node (ref "E2") (pin "9") (pinfunction "GND_9") (pintype "passive"))
      (node (ref "ENC_1") (pin "3") (pinfunction "3_3") (pintype "passive"))
      (node (ref "ENC_2") (pin "3") (pinfunction "3_3") (pintype "passive"))
      (node (ref "ENC_3") (pin "3") (pinfunction "3_3") (pintype "passive"))
      (node (ref "ENC_4") (pin "3") (pinfunction "3_3") (pintype "passive"))
      (node (ref "EXP1") (pin "9") (pinfunction "9_9") (pintype "passive"))
      (node (ref "EXP2") (pin "9") (pinfunction "9_9") (pintype "passive"))
      (node (ref "EXP3") (pin "3") (pinfunction "3_3") (pintype "passive"))
      (node (ref "EXP3") (pin "4") (pinfunction "4_4") (pintype "passive"))
      (node (ref "HB-PWR") (pin "1") (pinfunction "4_1") (pintype "power_in"))
      (node (ref "ISP1") (pin "6") (pinfunction "6_6") (pintype "passive"))
      (node (ref "ISP2") (pin "6") (pinfunction "6_6") (pintype "passive"))
      (node (ref "J2") (pin "GND") (pinfunction "GND_GND") (pintype "passive"))
      (node (ref "JTAG") (pin "10") (pinfunction "10_10") (pintype "passive"))
      (node (ref "JTAG") (pin "2") (pinfunction "2_2") (pintype "passive"))
      (node (ref "L1") (pin "2") (pinfunction "2_2") (pintype "passive"))
      (node (ref "LD1") (pin "2") (pinfunction "K_2") (pintype "passive"))
      (node (ref "LD10") (pin "2") (pinfunction "K_2") (pintype "passive"))
      (node (ref "LD2") (pin "2") (pinfunction "K_2") (pintype "passive"))
      (node (ref "LD3") (pin "2") (pinfunction "K_2") (pintype "passive"))
      (node (ref "LD4") (pin "2") (pinfunction "K_2") (pintype "passive"))
      (node (ref "LD5") (pin "2") (pinfunction "K_2") (pintype "passive"))
      (node (ref "LD6") (pin "2") (pinfunction "K_2") (pintype "passive"))
      (node (ref "LD7") (pin "2") (pinfunction "K_2") (pintype "passive"))
      (node (ref "LD8") (pin "2") (pinfunction "K_2") (pintype "passive"))
      (node (ref "LD9") (pin "2") (pinfunction "K_2") (pintype "passive"))
      (node (ref "LED1") (pin "2") (pinfunction "K_2") (pintype "passive"))
      (node (ref "MAIN-PWR") (pin "1") (pinfunction "4_1") (pintype "power_in"))
      (node (ref "PS_ON") (pin "2") (pinfunction "2_2") (pintype "passive"))
      (node (ref "PWR") (pin "2") (pinfunction "2_2") (pintype "passive"))
      (node (ref "Q1") (pin "3") (pinfunction "S_3") (pintype "passive"))
      (node (ref "Q2") (pin "3") (pinfunction "S_3") (pintype "passive"))
      (node (ref "Q3") (pin "3") (pinfunction "S_3") (pintype "passive"))
      (node (ref "Q4") (pin "3") (pinfunction "S_3") (pintype "passive"))
      (node (ref "Q5") (pin "3") (pinfunction "S_3") (pintype "passive"))
      (node (ref "Q6") (pin "3") (pinfunction "S_3") (pintype "passive"))
      (node (ref "R10") (pin "1") (pinfunction "1_1") (pintype "passive"))
      (node (ref "R14") (pin "2") (pinfunction "2_2") (pintype "passive"))
      (node (ref "R19") (pin "1") (pinfunction "1_1") (pintype "passive"))
      (node (ref "R22") (pin "2") (pinfunction "2_2") (pintype "passive"))
      (node (ref "R24") (pin "2") (pinfunction "2_2") (pintype "passive"))
      (node (ref "R26") (pin "2") (pinfunction "2_2") (pintype "passive"))
      (node (ref "R28") (pin "2") (pinfunction "2_2") (pintype "passive"))
      (node (ref "R30") (pin "2") (pinfunction "2_2") (pintype "passive"))
      (node (ref "R32") (pin "2") (pinfunction "2_2") (pintype "passive"))
      (node (ref "R35") (pin "2") (pinfunction "2_2") (pintype "passive"))
      (node (ref "R38") (pin "2") (pinfunction "2_2") (pintype "passive"))
      (node (ref "R44") (pin "2") (pinfunction "2_2") (pintype "passive"))
      (node (ref "R47") (pin "2") (pinfunction "2_2") (pintype "passive"))
      (node (ref "R49") (pin "2") (pinfunction "2_2") (pintype "passive"))
      (node (ref "R52") (pin "2") (pinfunction "2_2") (pintype "passive"))
      (node (ref "R57") (pin "1") (pinfunction "1_1") (pintype "passive"))
      (node (ref "R6") (pin "1") (pinfunction "1_1") (pintype "passive"))
      (node (ref "Reset") (pin "1") (pintype "passive"))
      (node (ref "Thermistors") (pin "1") (pinfunction "1_1") (pintype "passive"))
      (node (ref "Thermistors") (pin "3") (pinfunction "3_3") (pintype "passive"))
      (node (ref "Thermistors") (pin "5") (pinfunction "5_5") (pintype "passive"))
      (node (ref "Thermistors") (pin "7") (pinfunction "7_7") (pintype "passive"))
      (node (ref "Thermistors") (pin "9") (pinfunction "9_9") (pintype "passive"))
      (node (ref "U1") (pin "11") (pinfunction "GND_11") (pintype "passive"))
      (node (ref "U1") (pin "32") (pinfunction "GND_32") (pintype "passive"))
      (node (ref "U1") (pin "62") (pinfunction "GND_62") (pintype "passive"))
      (node (ref "U1") (pin "81") (pinfunction "GND_81") (pintype "passive"))
      (node (ref "U1") (pin "99") (pinfunction "AGND_99") (pintype "passive"))
      (node (ref "U2") (pin "28") (pinfunction "UGND_28") (pintype "passive"))
      (node (ref "U2") (pin "3") (pinfunction "GND_3") (pintype "passive"))
      (node (ref "U2") (pin "33") (pinfunction "PAD_33") (pintype "passive"))
      (node (ref "U3") (pin "2") (pinfunction "GND_2") (pintype "passive"))
      (node (ref "U4") (pin "3") (pinfunction "GND_3") (pintype "passive"))
      (node (ref "U5") (pin "2") (pinfunction "GND_2") (pintype "passive"))
      (node (ref "USB_AUX") (pin "2") (pinfunction "2_2") (pintype "passive"))
      (node (ref "X") (pin "15") (pinfunction "GND_15") (pintype "passive"))
      (node (ref "X") (pin "9") (pinfunction "GND_9") (pintype "passive"))
      (node (ref "X+") (pin "2") (pinfunction "2_2") (pintype "passive"))
      (node (ref "X-") (pin "2") (pinfunction "2_2") (pintype "passive"))
      (node (ref "Y") (pin "15") (pinfunction "GND_15") (pintype "passive"))
      (node (ref "Y") (pin "9") (pinfunction "GND_9") (pintype "passive"))
      (node (ref "Y+") (pin "2") (pinfunction "2_2") (pintype "passive"))
      (node (ref "Y-") (pin "2") (pinfunction "2_2") (pintype "passive"))
      (node (ref "Z") (pin "15") (pinfunction "GND_15") (pintype "passive"))
      (node (ref "Z") (pin "9") (pinfunction "GND_9") (pintype "passive"))
      (node (ref "Z+") (pin "2") (pinfunction "2_2") (pintype "passive"))
      (node (ref "Z-") (pin "2") (pinfunction "2_2") (pintype "passive"))
    )
    (net (code "84") (name "Net-(C10-Pad1)") (class "Default")
      (node (ref "C10") (pin "1") (pinfunction "1_1") (pintype "passive"))
      (node (ref "R19") (pin "2") (pinfunction "2_2") (pintype "passive"))
    )
    (net (code "85") (name "Net-(D4A-A)") (class "Default")
      (node (ref "D4") (pin "1") (pinfunction "A_1") (pintype "passive"))
      (node (ref "F3") (pin "2") (pinfunction "2_2") (pintype "passive"))
    )
    (net (code "86") (name "Net-(E0-1A)") (class "Default")
      (node (ref "E0") (pin "12") (pinfunction "1A_12") (pintype "passive"))
      (node (ref "E0_MOT") (pin "2") (pinfunction "2_2") (pintype "passive"))
      (node (ref "E0_MOT_A") (pin "3") (pinfunction "3_3") (pintype "passive"))
    )
    (net (code "87") (name "Net-(E0-1B)") (class "Default")
      (node (ref "E0") (pin "11") (pinfunction "1B_11") (pintype "passive"))
      (node (ref "E0_MOT") (pin "1") (pinfunction "1_1") (pintype "passive"))
      (node (ref "E0_MOT_A") (pin "4") (pinfunction "4_4") (pintype "passive"))
    )
    (net (code "88") (name "Net-(E0-2A)") (class "Default")
      (node (ref "E0") (pin "13") (pinfunction "2A_13") (pintype "passive"))
      (node (ref "E0_MOT") (pin "3") (pinfunction "3_3") (pintype "passive"))
      (node (ref "E0_MOT_A") (pin "2") (pinfunction "2_2") (pintype "passive"))
    )
    (net (code "89") (name "Net-(E0-2B)") (class "Default")
      (node (ref "E0") (pin "14") (pinfunction "2B_14") (pintype "passive"))
      (node (ref "E0_MOT") (pin "4") (pinfunction "4_4") (pintype "passive"))
      (node (ref "E0_MOT_A") (pin "1") (pinfunction "1_1") (pintype "passive"))
    )
    (net (code "90") (name "Net-(E0-MS1)") (class "Default")
      (node (ref "E0") (pin "2") (pinfunction "MS1_2") (pintype "passive"))
      (node (ref "E0_MS") (pin "4") (pinfunction "B3_4") (pintype "passive"))
      (node (ref "R28") (pin "1") (pinfunction "1_1") (pintype "passive"))
    )
    (net (code "91") (name "Net-(E0-MS2)") (class "Default")
      (node (ref "E0") (pin "3") (pinfunction "MS2_3") (pintype "passive"))
      (node (ref "E0_MS") (pin "5") (pinfunction "B2_5") (pintype "passive"))
    )
    (net (code "92") (name "Net-(E0-MS3)") (class "Default")
      (node (ref "E0") (pin "4") (pinfunction "MS3_4") (pintype "passive"))
      (node (ref "E0_MS") (pin "6") (pinfunction "B1_6") (pintype "passive"))
    )
    (net (code "93") (name "Net-(E0-~{RST})") (class "Default")
      (node (ref "E0") (pin "5") (pinfunction "~{RST}_5") (pintype "passive"))
      (node (ref "E0") (pin "6") (pinfunction "~{SLEEP}_6") (pintype "passive"))
    )
    (net (code "94") (name "Net-(E1-1A)") (class "Default")
      (node (ref "E1") (pin "12") (pinfunction "1A_12") (pintype "passive"))
      (node (ref "E1_MOT") (pin "2") (pinfunction "2_2") (pintype "passive"))
      (node (ref "E1_MOT_A") (pin "3") (pinfunction "3_3") (pintype "passive"))
    )
    (net (code "95") (name "Net-(E1-1B)") (class "Default")
      (node (ref "E1") (pin "11") (pinfunction "1B_11") (pintype "passive"))
      (node (ref "E1_MOT") (pin "1") (pinfunction "1_1") (pintype "passive"))
      (node (ref "E1_MOT_A") (pin "4") (pinfunction "4_4") (pintype "passive"))
    )
    (net (code "96") (name "Net-(E1-2A)") (class "Default")
      (node (ref "E1") (pin "13") (pinfunction "2A_13") (pintype "passive"))
      (node (ref "E1_MOT") (pin "3") (pinfunction "3_3") (pintype "passive"))
      (node (ref "E1_MOT_A") (pin "2") (pinfunction "2_2") (pintype "passive"))
    )
    (net (code "97") (name "Net-(E1-2B)") (class "Default")
      (node (ref "E1") (pin "14") (pinfunction "2B_14") (pintype "passive"))
      (node (ref "E1_MOT") (pin "4") (pinfunction "4_4") (pintype "passive"))
      (node (ref "E1_MOT_A") (pin "1") (pinfunction "1_1") (pintype "passive"))
    )
    (net (code "98") (name "Net-(E1-MS1)") (class "Default")
      (node (ref "E1") (pin "2") (pinfunction "MS1_2") (pintype "passive"))
      (node (ref "E1_MS") (pin "4") (pinfunction "B3_4") (pintype "passive"))
      (node (ref "R30") (pin "1") (pinfunction "1_1") (pintype "passive"))
    )
    (net (code "99") (name "Net-(E1-MS2)") (class "Default")
      (node (ref "E1") (pin "3") (pinfunction "MS2_3") (pintype "passive"))
      (node (ref "E1_MS") (pin "5") (pinfunction "B2_5") (pintype "passive"))
    )
    (net (code "100") (name "Net-(E1-MS3)") (class "Default")
      (node (ref "E1") (pin "4") (pinfunction "MS3_4") (pintype "passive"))
      (node (ref "E1_MS") (pin "6") (pinfunction "B1_6") (pintype "passive"))
    )
    (net (code "101") (name "Net-(E1-~{RST})") (class "Default")
      (node (ref "E1") (pin "5") (pinfunction "~{RST}_5") (pintype "passive"))
      (node (ref "E1") (pin "6") (pinfunction "~{SLEEP}_6") (pintype "passive"))
    )
    (net (code "102") (name "Net-(E2-1A)") (class "Default")
      (node (ref "E2") (pin "12") (pinfunction "1A_12") (pintype "passive"))
      (node (ref "E2_MOT") (pin "2") (pinfunction "2_2") (pintype "passive"))
      (node (ref "E2_MOT_A") (pin "3") (pinfunction "3_3") (pintype "passive"))
    )
    (net (code "103") (name "Net-(E2-1B)") (class "Default")
      (node (ref "E2") (pin "11") (pinfunction "1B_11") (pintype "passive"))
      (node (ref "E2_MOT") (pin "1") (pinfunction "1_1") (pintype "passive"))
      (node (ref "E2_MOT_A") (pin "4") (pinfunction "4_4") (pintype "passive"))
    )
    (net (code "104") (name "Net-(E2-2A)") (class "Default")
      (node (ref "E2") (pin "13") (pinfunction "2A_13") (pintype "passive"))
      (node (ref "E2_MOT") (pin "3") (pinfunction "3_3") (pintype "passive"))
      (node (ref "E2_MOT_A") (pin "2") (pinfunction "2_2") (pintype "passive"))
    )
    (net (code "105") (name "Net-(E2-2B)") (class "Default")
      (node (ref "E2") (pin "14") (pinfunction "2B_14") (pintype "passive"))
      (node (ref "E2_MOT") (pin "4") (pinfunction "4_4") (pintype "passive"))
      (node (ref "E2_MOT_A") (pin "1") (pinfunction "1_1") (pintype "passive"))
    )
    (net (code "106") (name "Net-(E2-MS1)") (class "Default")
      (node (ref "E2") (pin "2") (pinfunction "MS1_2") (pintype "passive"))
      (node (ref "E2_MS") (pin "4") (pinfunction "B3_4") (pintype "passive"))
      (node (ref "R44") (pin "1") (pinfunction "1_1") (pintype "passive"))
    )
    (net (code "107") (name "Net-(E2-MS2)") (class "Default")
      (node (ref "E2") (pin "3") (pinfunction "MS2_3") (pintype "passive"))
      (node (ref "E2_MS") (pin "5") (pinfunction "B2_5") (pintype "passive"))
    )
    (net (code "108") (name "Net-(E2-MS3)") (class "Default")
      (node (ref "E2") (pin "4") (pinfunction "MS3_4") (pintype "passive"))
      (node (ref "E2_MS") (pin "6") (pinfunction "B1_6") (pintype "passive"))
    )
    (net (code "109") (name "Net-(E2-~{RST})") (class "Default")
      (node (ref "E2") (pin "5") (pinfunction "~{RST}_5") (pintype "passive"))
      (node (ref "E2") (pin "6") (pinfunction "~{SLEEP}_6") (pintype "passive"))
    )
    (net (code "110") (name "Net-(F1-Pad0)") (class "Default")
      (node (ref "F1") (pin "0") (pinfunction "0_0") (pintype "passive"))
      (node (ref "HB-PWR") (pin "2") (pinfunction "2_2") (pintype "power_in"))
    )
    (net (code "111") (name "Net-(F2-Pad0)") (class "Default")
      (node (ref "F2") (pin "0") (pinfunction "0_0") (pintype "passive"))
      (node (ref "MAIN-PWR") (pin "2") (pinfunction "2_2") (pintype "power_in"))
    )
    (net (code "112") (name "Net-(FAN0-4)") (class "Default")
      (node (ref "D10") (pin "K") (pinfunction "K_K") (pintype "passive"))
      (node (ref "FAN0") (pin "1") (pinfunction "4_1") (pintype "power_in"))
      (node (ref "FAN0_1") (pin "1") (pinfunction "1_1") (pintype "passive"))
      (node (ref "VFA0_sel") (pin "2") (pinfunction "2_2") (pintype "passive"))
    )
    (net (code "113") (name "Net-(FAN1-4)") (class "Default")
      (node (ref "D11") (pin "K") (pinfunction "K_K") (pintype "passive"))
      (node (ref "FAN1") (pin "1") (pinfunction "4_1") (pintype "power_in"))
      (node (ref "FAN1_1") (pin "1") (pinfunction "1_1") (pintype "passive"))
      (node (ref "VFA1_sel") (pin "2") (pinfunction "2_2") (pintype "passive"))
    )
    (net (code "114") (name "Net-(HB-OUT-4)") (class "Default")
      (node (ref "D13") (pin "A") (pinfunction "A_A") (pintype "passive"))
      (node (ref "HB-OUT") (pin "1") (pinfunction "4_1") (pintype "power_in"))
      (node (ref "Q6") (pin "2") (pinfunction "D_2") (pintype "passive"))
    )
    (net (code "115") (name "Net-(HE2-4)") (class "Default")
      (node (ref "D14") (pin "K") (pinfunction "K_K") (pintype "passive"))
      (node (ref "HE2") (pin "1") (pinfunction "4_1") (pintype "power_in"))
      (node (ref "VHE2_sel") (pin "2") (pinfunction "2_2") (pintype "passive"))
    )
    (net (code "116") (name "Net-(J2-SH)") (class "Default")
      (node (ref "J2") (pin "SHIELD") (pinfunction "SH_SHIELD") (pintype "passive"))
      (node (ref "L1") (pin "1") (pinfunction "1_1") (pintype "passive"))
      (node (ref "USB_AUX") (pin "1") (pinfunction "1_1") (pintype "passive"))
    )
    (net (code "117") (name "Net-(LD1-A)") (class "Default")
      (node (ref "LD1") (pin "1") (pinfunction "A_1") (pintype "passive"))
      (node (ref "R4") (pin "1") (pinfunction "1_1") (pintype "passive"))
    )
    (net (code "118") (name "Net-(LD2-A)") (class "Default")
      (node (ref "LD2") (pin "1") (pinfunction "A_1") (pintype "passive"))
      (node (ref "R33") (pin "1") (pinfunction "1_1") (pintype "passive"))
    )
    (net (code "119") (name "Net-(LD3-A)") (class "Default")
      (node (ref "LD3") (pin "1") (pinfunction "A_1") (pintype "passive"))
      (node (ref "R36") (pin "1") (pinfunction "1_1") (pintype "passive"))
    )
    (net (code "120") (name "Net-(LD4-A)") (class "Default")
      (node (ref "LD4") (pin "1") (pinfunction "A_1") (pintype "passive"))
      (node (ref "R39") (pin "1") (pinfunction "1_1") (pintype "passive"))
    )
    (net (code "121") (name "Net-(LD5-A)") (class "Default")
      (node (ref "LD5") (pin "1") (pinfunction "A_1") (pintype "passive"))
      (node (ref "R50") (pin "1") (pinfunction "1_1") (pintype "passive"))
    )
    (net (code "122") (name "Net-(LD6-A)") (class "Default")
      (node (ref "LD6") (pin "1") (pinfunction "A_1") (pintype "passive"))
      (node (ref "R53") (pin "1") (pinfunction "1_1") (pintype "passive"))
    )
    (net (code "123") (name "Net-(LD7-A)") (class "Default")
      (node (ref "LD7") (pin "1") (pinfunction "A_1") (pintype "passive"))
      (node (ref "R55") (pin "1") (pinfunction "1_1") (pintype "passive"))
    )
    (net (code "124") (name "Net-(LD8-A)") (class "Default")
      (node (ref "LD8") (pin "1") (pinfunction "A_1") (pintype "passive"))
      (node (ref "R20") (pin "1") (pinfunction "1_1") (pintype "passive"))
    )
    (net (code "125") (name "Net-(LD9-A)") (class "Default")
      (node (ref "LD9") (pin "1") (pinfunction "A_1") (pintype "passive"))
      (node (ref "R58") (pin "1") (pinfunction "1_1") (pintype "passive"))
    )
    (net (code "126") (name "Net-(LD10-A)") (class "Default")
      (node (ref "LD10") (pin "1") (pinfunction "A_1") (pintype "passive"))
      (node (ref "R59") (pin "1") (pinfunction "1_1") (pintype "passive"))
    )
    (net (code "127") (name "Net-(LED1-A)") (class "Default")
      (node (ref "LED1") (pin "1") (pinfunction "A_1") (pintype "passive"))
      (node (ref "R13") (pin "1") (pinfunction "1_1") (pintype "passive"))
    )
    (net (code "128") (name "Net-(Q1-D)") (class "Default")
      (node (ref "D12") (pin "A") (pinfunction "A_A") (pintype "passive"))
      (node (ref "HE0") (pin "2") (pinfunction "2_2") (pintype "power_in"))
      (node (ref "Q1") (pin "2") (pinfunction "D_2") (pintype "passive"))
    )
    (net (code "129") (name "Net-(Q1-G)") (class "Default")
      (node (ref "Q1") (pin "1") (pinfunction "G_1") (pintype "passive"))
      (node (ref "R34") (pin "2") (pinfunction "2_2") (pintype "passive"))
    )
    (net (code "130") (name "Net-(Q2-D)") (class "Default")
      (node (ref "D9") (pin "A") (pinfunction "A_A") (pintype "passive"))
      (node (ref "HE1") (pin "2") (pinfunction "2_2") (pintype "power_in"))
      (node (ref "Q2") (pin "2") (pinfunction "D_2") (pintype "passive"))
    )
    (net (code "131") (name "Net-(Q2-G)") (class "Default")
      (node (ref "Q2") (pin "1") (pinfunction "G_1") (pintype "passive"))
      (node (ref "R37") (pin "2") (pinfunction "2_2") (pintype "passive"))
    )
    (net (code "132") (name "Net-(Q3-D)") (class "Default")
      (node (ref "D14") (pin "A") (pinfunction "A_A") (pintype "passive"))
      (node (ref "HE2") (pin "2") (pinfunction "2_2") (pintype "power_in"))
      (node (ref "Q3") (pin "2") (pinfunction "D_2") (pintype "passive"))
    )
    (net (code "133") (name "Net-(Q3-G)") (class "Default")
      (node (ref "Q3") (pin "1") (pinfunction "G_1") (pintype "passive"))
      (node (ref "R48") (pin "2") (pinfunction "2_2") (pintype "passive"))
    )
    (net (code "134") (name "Net-(Q4-D)") (class "Default")
      (node (ref "D10") (pin "A") (pinfunction "A_A") (pintype "passive"))
      (node (ref "FAN0") (pin "2") (pinfunction "2_2") (pintype "power_in"))
      (node (ref "FAN0_1") (pin "2") (pinfunction "2_2") (pintype "passive"))
      (node (ref "Q4") (pin "2") (pinfunction "D_2") (pintype "passive"))
    )
    (net (code "135") (name "Net-(Q4-G)") (class "Default")
      (node (ref "Q4") (pin "1") (pinfunction "G_1") (pintype "passive"))
      (node (ref "R51") (pin "2") (pinfunction "2_2") (pintype "passive"))
    )
    (net (code "136") (name "Net-(Q5-D)") (class "Default")
      (node (ref "D11") (pin "A") (pinfunction "A_A") (pintype "passive"))
      (node (ref "FAN1") (pin "2") (pinfunction "2_2") (pintype "power_in"))
      (node (ref "FAN1_1") (pin "2") (pinfunction "2_2") (pintype "passive"))
      (node (ref "Q5") (pin "2") (pinfunction "D_2") (pintype "passive"))
    )
    (net (code "137") (name "Net-(Q5-G)") (class "Default")
      (node (ref "Q5") (pin "1") (pinfunction "G_1") (pintype "passive"))
      (node (ref "R46") (pin "2") (pinfunction "2_2") (pintype "passive"))
    )
    (net (code "138") (name "Net-(Q6-G)") (class "Default")
      (node (ref "Q6") (pin "1") (pinfunction "G_1") (pintype "passive"))
      (node (ref "R31") (pin "2") (pinfunction "2_2") (pintype "passive"))
    )
    (net (code "139") (name "Net-(RX-A)") (class "Default")
      (node (ref "R16") (pin "2") (pinfunction "2_2") (pintype "passive"))
      (node (ref "RX") (pin "1") (pinfunction "A_1") (pintype "passive"))
    )
    (net (code "140") (name "Net-(RX-K)") (class "Default")
      (node (ref "RX") (pin "2") (pinfunction "K_2") (pintype "passive"))
      (node (ref "U2") (pin "10") (pinfunction "(INT5/AIN3)PD4_10") (pintype "passive"))
    )
    (net (code "141") (name "Net-(TX-A)") (class "Default")
      (node (ref "R15") (pin "2") (pinfunction "2_2") (pintype "passive"))
      (node (ref "TX") (pin "1") (pinfunction "A_1") (pintype "passive"))
    )
    (net (code "142") (name "Net-(TX-K)") (class "Default")
      (node (ref "TX") (pin "2") (pinfunction "K_2") (pintype "passive"))
      (node (ref "U2") (pin "11") (pinfunction "(XCK/AIN4/PCINT12)PD5_11") (pintype "passive"))
    )
    (net (code "143") (name "Net-(U1-XTAL1)") (class "Default")
      (node (ref "C20") (pin "2") (pinfunction "2_2") (pintype "passive"))
      (node (ref "R1") (pin "1") (pinfunction "1_1") (pintype "passive"))
      (node (ref "U1") (pin "34") (pinfunction "XTAL1_34") (pintype "passive"))
      (node (ref "Y1") (pin "1") (pinfunction "OSC1_1") (pintype "passive"))
    )
    (net (code "144") (name "Net-(U1-XTAL2)") (class "Default")
      (node (ref "C19") (pin "2") (pinfunction "2_2") (pintype "passive"))
      (node (ref "R1") (pin "2") (pinfunction "2_2") (pintype "passive"))
      (node (ref "U1") (pin "33") (pinfunction "XTAL2_33") (pintype "passive"))
      (node (ref "Y1") (pin "3") (pinfunction "OSC2_3") (pintype "passive"))
    )
    (net (code "145") (name "Net-(U2-(RXD1{slash}AIN1{slash}INT2)PD2)") (class "Default")
      (node (ref "R17") (pin "1") (pinfunction "1_1") (pintype "passive"))
      (node (ref "U2") (pin "8") (pinfunction "(RXD1/AIN1/INT2)PD2_8") (pintype "passive"))
    )
    (net (code "146") (name "Net-(U2-(TXD1{slash}INT3)PD3)") (class "Default")
      (node (ref "R18") (pin "1") (pinfunction "1_1") (pintype "passive"))
      (node (ref "U2") (pin "9") (pinfunction "(TXD1/INT3)PD3_9") (pintype "passive"))
    )
    (net (code "147") (name "Net-(U2-D+)") (class "Default")
      (node (ref "R8") (pin "1") (pinfunction "1_1") (pintype "passive"))
      (node (ref "U2") (pin "29") (pinfunction "D+_29") (pintype "passive"))
    )
    (net (code "148") (name "Net-(U2-D-)") (class "Default")
      (node (ref "R7") (pin "1") (pinfunction "1_1") (pintype "passive"))
      (node (ref "U2") (pin "30") (pinfunction "D-_30") (pintype "passive"))
    )
    (net (code "149") (name "Net-(U2-UCAP)") (class "Default")
      (node (ref "C12") (pin "1") (pintype "passive"))
      (node (ref "U2") (pin "27") (pinfunction "UCAP_27") (pintype "passive"))
    )
    (net (code "150") (name "Net-(U2-XTAL1)") (class "Default")
      (node (ref "C14") (pin "2") (pinfunction "2_2") (pintype "passive"))
      (node (ref "R9") (pin "1") (pinfunction "1_1") (pintype "passive"))
      (node (ref "U2") (pin "1") (pinfunction "XTAL1_1") (pintype "passive"))
      (node (ref "Y2") (pin "1") (pinfunction "OSC1_1") (pintype "passive"))
    )
    (net (code "151") (name "Net-(U2-XTAL2(PC0))") (class "Default")
      (node (ref "C15") (pin "2") (pinfunction "2_2") (pintype "passive"))
      (node (ref "R9") (pin "2") (pinfunction "2_2") (pintype "passive"))
      (node (ref "U2") (pin "2") (pinfunction "XTAL2(PC0)_2") (pintype "passive"))
      (node (ref "Y2") (pin "3") (pinfunction "OSC2_3") (pintype "passive"))
    )
    (net (code "152") (name "Net-(U3-BST)") (class "Default")
      (node (ref "C18") (pin "2") (pinfunction "2_2") (pintype "passive"))
      (node (ref "U3") (pin "1") (pinfunction "BST_1") (pintype "passive"))
    )
    (net (code "153") (name "Net-(U3-SW)") (class "Default")
      (node (ref "C18") (pin "1") (pinfunction "1_1") (pintype "passive"))
      (node (ref "D5") (pin "K") (pinfunction "K_K") (pintype "passive"))
      (node (ref "L3") (pin "1") (pinfunction "1_1") (pintype "passive"))
      (node (ref "U3") (pin "6") (pinfunction "SW_6") (pintype "passive"))
    )
    (net (code "154") (name "Net-(U4-BST)") (class "Default")
      (node (ref "C33") (pin "1") (pinfunction "1_1") (pintype "passive"))
      (node (ref "U4") (pin "2") (pinfunction "BST_2") (pintype "passive"))
    )
    (net (code "155") (name "Net-(U4-COMP)") (class "Default")
      (node (ref "C10") (pin "2") (pinfunction "2_2") (pintype "passive"))
      (node (ref "U4") (pin "5") (pinfunction "COMP_5") (pintype "passive"))
    )
    (net (code "156") (name "Net-(U4-FSW)") (class "Default")
      (node (ref "R10") (pin "2") (pinfunction "2_2") (pintype "passive"))
      (node (ref "U4") (pin "4") (pinfunction "FSW_4") (pintype "passive"))
    )
    (net (code "157") (name "Net-(U4-LX)") (class "Default")
      (node (ref "C33") (pin "2") (pinfunction "2_2") (pintype "passive"))
      (node (ref "D8") (pin "K") (pinfunction "K_K") (pintype "passive"))
      (node (ref "L4") (pin "1") (pinfunction "1_1") (pintype "passive"))
      (node (ref "U4") (pin "1") (pinfunction "LX_1") (pintype "passive"))
    )
    (net (code "158") (name "Net-(U4-SS)") (class "Default")
      (node (ref "C34") (pin "2") (pinfunction "2_2") (pintype "passive"))
      (node (ref "U4") (pin "7") (pinfunction "SS_7") (pintype "passive"))
    )
    (net (code "159") (name "Net-(U5-IO1)") (class "Default")
      (node (ref "J2") (pin "D-") (pinfunction "D-_D-") (pintype "passive"))
      (node (ref "R7") (pin "2") (pinfunction "2_2") (pintype "passive"))
      (node (ref "U5") (pin "1") (pinfunction "IO1_1") (pintype "passive"))
      (node (ref "USB_AUX") (pin "4") (pinfunction "4_4") (pintype "passive"))
    )
    (net (code "160") (name "Net-(U5-IO2)") (class "Default")
      (node (ref "J2") (pin "D+") (pinfunction "D+_D+") (pintype "passive"))
      (node (ref "R8") (pin "2") (pinfunction "2_2") (pintype "passive"))
      (node (ref "U5") (pin "3") (pinfunction "IO2_3") (pintype "passive"))
      (node (ref "USB_AUX") (pin "3") (pinfunction "3_3") (pintype "passive"))
    )
    (net (code "161") (name "Net-(X-1A)") (class "Default")
      (node (ref "X") (pin "12") (pinfunction "1A_12") (pintype "passive"))
      (node (ref "X_MOT") (pin "2") (pinfunction "2_2") (pintype "passive"))
      (node (ref "X_MOT_A") (pin "3") (pinfunction "3_3") (pintype "passive"))
    )
    (net (code "162") (name "Net-(X-1B)") (class "Default")
      (node (ref "X") (pin "11") (pinfunction "1B_11") (pintype "passive"))
      (node (ref "X_MOT") (pin "1") (pinfunction "1_1") (pintype "passive"))
      (node (ref "X_MOT_A") (pin "4") (pinfunction "4_4") (pintype "passive"))
    )
    (net (code "163") (name "Net-(X-2A)") (class "Default")
      (node (ref "X") (pin "13") (pinfunction "2A_13") (pintype "passive"))
      (node (ref "X_MOT") (pin "3") (pinfunction "3_3") (pintype "passive"))
      (node (ref "X_MOT_A") (pin "2") (pinfunction "2_2") (pintype "passive"))
    )
    (net (code "164") (name "Net-(X-2B)") (class "Default")
      (node (ref "X") (pin "14") (pinfunction "2B_14") (pintype "passive"))
      (node (ref "X_MOT") (pin "4") (pinfunction "4_4") (pintype "passive"))
      (node (ref "X_MOT_A") (pin "1") (pinfunction "1_1") (pintype "passive"))
    )
    (net (code "165") (name "Net-(X-MS1)") (class "Default")
      (node (ref "R22") (pin "1") (pinfunction "1_1") (pintype "passive"))
      (node (ref "X") (pin "2") (pinfunction "MS1_2") (pintype "passive"))
      (node (ref "X_MS") (pin "4") (pinfunction "B3_4") (pintype "passive"))
    )
    (net (code "166") (name "Net-(X-MS2)") (class "Default")
      (node (ref "X") (pin "3") (pinfunction "MS2_3") (pintype "passive"))
      (node (ref "X_MS") (pin "5") (pinfunction "B2_5") (pintype "passive"))
    )
    (net (code "167") (name "Net-(X-MS3)") (class "Default")
      (node (ref "X") (pin "4") (pinfunction "MS3_4") (pintype "passive"))
      (node (ref "X_MS") (pin "6") (pinfunction "B1_6") (pintype "passive"))
    )
    (net (code "168") (name "Net-(X-~{RST})") (class "Default")
      (node (ref "X") (pin "5") (pinfunction "~{RST}_5") (pintype "passive"))
      (node (ref "X") (pin "6") (pinfunction "~{SLEEP}_6") (pintype "passive"))
    )
    (net (code "169") (name "Net-(Y-1A)") (class "Default")
      (node (ref "Y") (pin "12") (pinfunction "1A_12") (pintype "passive"))
      (node (ref "Y_MOT") (pin "2") (pinfunction "2_2") (pintype "passive"))
      (node (ref "Y_MOT_A") (pin "3") (pinfunction "3_3") (pintype "passive"))
    )
    (net (code "170") (name "Net-(Y-1B)") (class "Default")
      (node (ref "Y") (pin "11") (pinfunction "1B_11") (pintype "passive"))
      (node (ref "Y_MOT") (pin "1") (pinfunction "1_1") (pintype "passive"))
      (node (ref "Y_MOT_A") (pin "4") (pinfunction "4_4") (pintype "passive"))
    )
    (net (code "171") (name "Net-(Y-2A)") (class "Default")
      (node (ref "Y") (pin "13") (pinfunction "2A_13") (pintype "passive"))
      (node (ref "Y_MOT") (pin "3") (pinfunction "3_3") (pintype "passive"))
      (node (ref "Y_MOT_A") (pin "2") (pinfunction "2_2") (pintype "passive"))
    )
    (net (code "172") (name "Net-(Y-2B)") (class "Default")
      (node (ref "Y") (pin "14") (pinfunction "2B_14") (pintype "passive"))
      (node (ref "Y_MOT") (pin "4") (pinfunction "4_4") (pintype "passive"))
      (node (ref "Y_MOT_A") (pin "1") (pinfunction "1_1") (pintype "passive"))
    )
    (net (code "173") (name "Net-(Y-MS1)") (class "Default")
      (node (ref "R24") (pin "1") (pinfunction "1_1") (pintype "passive"))
      (node (ref "Y") (pin "2") (pinfunction "MS1_2") (pintype "passive"))
      (node (ref "Y_MS") (pin "4") (pinfunction "B3_4") (pintype "passive"))
    )
    (net (code "174") (name "Net-(Y-MS2)") (class "Default")
      (node (ref "Y") (pin "3") (pinfunction "MS2_3") (pintype "passive"))
      (node (ref "Y_MS") (pin "5") (pinfunction "B2_5") (pintype "passive"))
    )
    (net (code "175") (name "Net-(Y-MS3)") (class "Default")
      (node (ref "Y") (pin "4") (pinfunction "MS3_4") (pintype "passive"))
      (node (ref "Y_MS") (pin "6") (pinfunction "B1_6") (pintype "passive"))
    )
    (net (code "176") (name "Net-(Y-~{RST})") (class "Default")
      (node (ref "Y") (pin "5") (pinfunction "~{RST}_5") (pintype "passive"))
      (node (ref "Y") (pin "6") (pinfunction "~{SLEEP}_6") (pintype "passive"))
    )
    (net (code "177") (name "Net-(Z-1A)") (class "Default")
      (node (ref "Z") (pin "12") (pinfunction "1A_12") (pintype "passive"))
      (node (ref "Z_MOT") (pin "2") (pinfunction "2_2") (pintype "passive"))
      (node (ref "Z_MOT_A") (pin "3") (pinfunction "3_3") (pintype "passive"))
    )
    (net (code "178") (name "Net-(Z-1B)") (class "Default")
      (node (ref "Z") (pin "11") (pinfunction "1B_11") (pintype "passive"))
      (node (ref "Z_MOT") (pin "1") (pinfunction "1_1") (pintype "passive"))
      (node (ref "Z_MOT_A") (pin "4") (pinfunction "4_4") (pintype "passive"))
    )
    (net (code "179") (name "Net-(Z-2A)") (class "Default")
      (node (ref "Z") (pin "13") (pinfunction "2A_13") (pintype "passive"))
      (node (ref "Z_MOT") (pin "3") (pinfunction "3_3") (pintype "passive"))
      (node (ref "Z_MOT_A") (pin "2") (pinfunction "2_2") (pintype "passive"))
    )
    (net (code "180") (name "Net-(Z-2B)") (class "Default")
      (node (ref "Z") (pin "14") (pinfunction "2B_14") (pintype "passive"))
      (node (ref "Z_MOT") (pin "4") (pinfunction "4_4") (pintype "passive"))
      (node (ref "Z_MOT_A") (pin "1") (pinfunction "1_1") (pintype "passive"))
    )
    (net (code "181") (name "Net-(Z-MS1)") (class "Default")
      (node (ref "R26") (pin "1") (pinfunction "1_1") (pintype "passive"))
      (node (ref "Z") (pin "2") (pinfunction "MS1_2") (pintype "passive"))
      (node (ref "Z_MS") (pin "4") (pinfunction "B3_4") (pintype "passive"))
    )
    (net (code "182") (name "Net-(Z-MS2)") (class "Default")
      (node (ref "Z") (pin "3") (pinfunction "MS2_3") (pintype "passive"))
      (node (ref "Z_MS") (pin "5") (pinfunction "B2_5") (pintype "passive"))
    )
    (net (code "183") (name "Net-(Z-MS3)") (class "Default")
      (node (ref "Z") (pin "4") (pinfunction "MS3_4") (pintype "passive"))
      (node (ref "Z_MS") (pin "6") (pinfunction "B1_6") (pintype "passive"))
    )
    (net (code "184") (name "Net-(Z-~{RST})") (class "Default")
      (node (ref "Z") (pin "5") (pinfunction "~{RST}_5") (pintype "passive"))
      (node (ref "Z") (pin "6") (pinfunction "~{SLEEP}_6") (pintype "passive"))
    )
    (net (code "185") (name "USBVCC") (class "Default")
      (node (ref "C11") (pin "2") (pinfunction "2_2") (pintype "passive"))
      (node (ref "F3") (pin "1") (pinfunction "1_1") (pintype "passive"))
      (node (ref "J2") (pin "VBUS") (pinfunction "VBUS_VBUS") (pintype "passive"))
      (node (ref "R4") (pin "2") (pinfunction "2_2") (pintype "passive"))
      (node (ref "U2") (pin "31") (pinfunction "UVCC_31") (pintype "passive"))
      (node (ref "U5") (pin "5") (pinfunction "VBUS_5") (pintype "passive"))
      (node (ref "USB_AUX") (pin "5") (pinfunction "5_5") (pintype "passive"))
    )
    (net (code "186") (name "VIN") (class "Default")
      (node (ref "C1") (pin "1") (pinfunction "1_1") (pintype "passive"))
      (node (ref "C3") (pin "1") (pintype "passive"))
      (node (ref "D1") (pin "K") (pinfunction "K_K") (pintype "passive"))
      (node (ref "U3") (pin "4") (pinfunction "~{SHDN}_4") (pintype "passive"))
      (node (ref "U3") (pin "5") (pinfunction "Vin_5") (pintype "passive"))
    )
    (net (code "187") (name "VIN1") (class "Default")
      (node (ref "C17") (pin "2") (pinfunction "2_2") (pintype "passive"))
      (node (ref "C21") (pin "1") (pinfunction "1_1") (pintype "passive"))
      (node (ref "C22") (pin "1") (pinfunction "1_1") (pintype "passive"))
      (node (ref "C23") (pin "1") (pinfunction "1_1") (pintype "passive"))
      (node (ref "C24") (pin "1") (pinfunction "1_1") (pintype "passive"))
      (node (ref "C25") (pin "1") (pinfunction "1_1") (pintype "passive"))
      (node (ref "C30") (pin "1") (pinfunction "1_1") (pintype "passive"))
      (node (ref "C31") (pin "1") (pinfunction "1_1") (pintype "passive"))
      (node (ref "D1") (pin "A") (pinfunction "A_A") (pintype "passive"))
      (node (ref "D12") (pin "K") (pinfunction "K_K") (pintype "passive"))
      (node (ref "D6") (pin "K") (pinfunction "K_K") (pintype "passive"))
      (node (ref "D9") (pin "K") (pinfunction "K_K") (pintype "passive"))
      (node (ref "E0") (pin "16") (pinfunction "VMOT_16") (pintype "passive"))
      (node (ref "E1") (pin "16") (pinfunction "VMOT_16") (pintype "passive"))
      (node (ref "E2") (pin "16") (pinfunction "VMOT_16") (pintype "passive"))
      (node (ref "F2") (pin "1") (pinfunction "1_1") (pintype "passive"))
      (node (ref "HE0") (pin "1") (pinfunction "4_1") (pintype "power_in"))
      (node (ref "HE1") (pin "1") (pinfunction "4_1") (pintype "power_in"))
      (node (ref "PWR") (pin "1") (pinfunction "1_1") (pintype "passive"))
      (node (ref "U4") (pin "9") (pinfunction "VIN_9") (pintype "passive"))
      (node (ref "VFA0_sel") (pin "1") (pinfunction "1_1") (pintype "passive"))
      (node (ref "VFA1_sel") (pin "1") (pinfunction "1_1") (pintype "passive"))
      (node (ref "VHE2_sel") (pin "1") (pinfunction "1_1") (pintype "passive"))
      (node (ref "X") (pin "16") (pinfunction "VMOT_16") (pintype "passive"))
      (node (ref "Y") (pin "16") (pinfunction "VMOT_16") (pintype "passive"))
      (node (ref "Z") (pin "16") (pinfunction "VMOT_16") (pintype "passive"))
    )
    (net (code "188") (name "VIN2") (class "Default")
      (node (ref "D13") (pin "K") (pinfunction "K_K") (pintype "passive"))
      (node (ref "D7") (pin "K") (pinfunction "K_K") (pintype "passive"))
      (node (ref "F1") (pin "1") (pinfunction "1_1") (pintype "passive"))
      (node (ref "HB-OUT") (pin "2") (pinfunction "2_2") (pintype "power_in"))
    )
    (net (code "189") (name "unconnected-(J2-PadID)") (class "Default")
      (node (ref "J2") (pin "ID") (pinfunction "ID_ID") (pintype "passive"))
    )
    (net (code "190") (name "unconnected-(JTAG-Pad8)") (class "Default")
      (node (ref "JTAG") (pin "8") (pinfunction "8_8") (pintype "passive+no_connect"))
    )
    (net (code "191") (name "unconnected-(U1-(CLKO{slash}ICP3{slash}INT7)PE7-Pad9)") (class "Default")
      (node (ref "U1") (pin "9") (pinfunction "(CLKO/ICP3/INT7)PE7_9") (pintype "passive+no_connect"))
    )
    (net (code "192") (name "unconnected-(U1-(ICP1)PD4-Pad47)") (class "Default")
      (node (ref "U1") (pin "47") (pinfunction "(ICP1)PD4_47") (pintype "passive+no_connect"))
    )
    (net (code "193") (name "unconnected-(U1-(OC2A{slash}PCINT4)PB4-Pad23)") (class "Default")
      (node (ref "U1") (pin "23") (pinfunction "(OC2A/PCINT4)PB4_23") (pintype "passive"))
    )
    (net (code "194") (name "unconnected-(U1-(T1)PD6-Pad49)") (class "Default")
      (node (ref "U1") (pin "49") (pinfunction "(T1)PD6_49") (pintype "passive+no_connect"))
    )
    (net (code "195") (name "unconnected-(U1-(T3{slash}INT6)PE6-Pad8)") (class "Default")
      (node (ref "U1") (pin "8") (pinfunction "(T3/INT6)PE6_8") (pintype "passive+no_connect"))
    )
    (net (code "196") (name "unconnected-(U1-(TOSC1)PG4-Pad29)") (class "Default")
      (node (ref "U1") (pin "29") (pinfunction "(TOSC1)PG4_29") (pintype "passive+no_connect"))
    )
    (net (code "197") (name "unconnected-(U1-(TOSC2)PG3-Pad28)") (class "Default")
      (node (ref "U1") (pin "28") (pinfunction "(TOSC2)PG3_28") (pintype "passive+no_connect"))
    )
    (net (code "198") (name "unconnected-(U1-(XCK1)PD5-Pad48)") (class "Default")
      (node (ref "U1") (pin "48") (pinfunction "(XCK1)PD5_48") (pintype "passive+no_connect"))
    )
    (net (code "199") (name "unconnected-(U1-PH2(XCK2)-Pad14)") (class "Default")
      (node (ref "U1") (pin "14") (pinfunction "PH2(XCK2)_14") (pintype "passive+no_connect"))
    )
    (net (code "200") (name "unconnected-(U1-PH7(T4)-Pad27)") (class "Default")
      (node (ref "U1") (pin "27") (pinfunction "PH7(T4)_27") (pintype "passive+no_connect"))
    )
    (net (code "201") (name "unconnected-(U1-PJ2(XCK3{slash}PCINT11)-Pad65)") (class "Default")
      (node (ref "U1") (pin "65") (pinfunction "PJ2(XCK3/PCINT11)_65") (pintype "passive+no_connect"))
    )
    (net (code "202") (name "unconnected-(U1-PJ3(PCINT12)-Pad66)") (class "Default")
      (node (ref "U1") (pin "66") (pinfunction "PJ3(PCINT12)_66") (pintype "passive+no_connect"))
    )
    (net (code "203") (name "unconnected-(U1-PJ4(PCINT13)-Pad67)") (class "Default")
      (node (ref "U1") (pin "67") (pinfunction "PJ4(PCINT13)_67") (pintype "passive+no_connect"))
    )
    (net (code "204") (name "unconnected-(U1-PJ5(PCINT14)-Pad68)") (class "Default")
      (node (ref "U1") (pin "68") (pinfunction "PJ5(PCINT14)_68") (pintype "passive+no_connect"))
    )
    (net (code "205") (name "unconnected-(U1-PJ6(PCINT15)-Pad69)") (class "Default")
      (node (ref "U1") (pin "69") (pinfunction "PJ6(PCINT15)_69") (pintype "passive+no_connect"))
    )
    (net (code "206") (name "unconnected-(U1-PJ7-Pad79)") (class "Default")
      (node (ref "U1") (pin "79") (pinfunction "PJ7_79") (pintype "passive+no_connect"))
    )
    (net (code "207") (name "unconnected-(U2-(AIN0{slash}INT1)PD1-Pad7)") (class "Default")
      (node (ref "U2") (pin "7") (pinfunction "(AIN0/INT1)PD1_7") (pintype "passive+no_connect"))
    )
    (net (code "208") (name "unconnected-(U2-(AIN2{slash}PCINT11)PC2-Pad5)") (class "Default")
      (node (ref "U2") (pin "5") (pinfunction "(AIN2/PCINT11)PC2_5") (pintype "passive+no_connect"))
    )
    (net (code "209") (name "unconnected-(U2-(INT4{slash}ICP1{slash}CLK0)PC7-Pad22)") (class "Default")
      (node (ref "U2") (pin "22") (pinfunction "(INT4/ICP1/CLK0)PC7_22") (pintype "passive+no_connect"))
    )
    (net (code "210") (name "unconnected-(U2-(OC0B{slash}INT0)PD0-Pad6)") (class "Default")
      (node (ref "U2") (pin "6") (pinfunction "(OC0B/INT0)PD0_6") (pintype "passive+no_connect"))
    )
    (net (code "211") (name "unconnected-(U2-(OC1A{slash}PCINT8)PC6-Pad23)") (class "Default")
      (node (ref "U2") (pin "23") (pinfunction "(OC1A/PCINT8)PC6_23") (pintype "passive+no_connect"))
    )
    (net (code "212") (name "unconnected-(U2-(PCINT5)PB5-Pad19)") (class "Default")
      (node (ref "U2") (pin "19") (pinfunction "(PCINT5)PB5_19") (pintype "passive+no_connect"))
    )
    (net (code "213") (name "unconnected-(U2-(PCINT6)PB6-Pad20)") (class "Default")
      (node (ref "U2") (pin "20") (pinfunction "(PCINT6)PB6_20") (pintype "passive+no_connect"))
    )
    (net (code "214") (name "unconnected-(U2-(PCINT7{slash}OC0A{slash}OC1C)PB7-Pad21)") (class "Default")
      (node (ref "U2") (pin "21") (pinfunction "(PCINT7/OC0A/OC1C)PB7_21") (pintype "passive+no_connect"))
    )
    (net (code "215") (name "unconnected-(U2-(PCINT9{slash}OC1B)PC5-Pad25)") (class "Default")
      (node (ref "U2") (pin "25") (pinfunction "(PCINT9/OC1B)PC5_25") (pintype "passive+no_connect"))
    )
    (net (code "216") (name "unconnected-(U2-(PCINT10)PC4-Pad26)") (class "Default")
      (node (ref "U2") (pin "26") (pinfunction "(PCINT10)PC4_26") (pintype "passive+no_connect"))
    )
    (net (code "217") (name "unconnected-(U2-(RTS{slash}AIN5{slash}INT6)PD6-Pad12)") (class "Default")
      (node (ref "U2") (pin "12") (pinfunction "(RTS/AIN5/INT6)PD6_12") (pintype "passive+no_connect"))
    )
    (net (code "218") (name "unconnected-(U2-(SS{slash}PCINT0)PB0-Pad14)") (class "Default")
      (node (ref "U2") (pin "14") (pinfunction "(SS/PCINT0)PB0_14") (pintype "passive+no_connect"))
    )
    (net (code "219") (name "unconnected-(U2-(T1{slash}PCINT4)PB4-Pad18)") (class "Default")
      (node (ref "U2") (pin "18") (pinfunction "(T1/PCINT4)PB4_18") (pintype "passive+no_connect"))
    )
    (net (code "220") (name "unconnected-(U5-IO3-Pad4)") (class "Default")
      (node (ref "U5") (pin "4") (pinfunction "IO3_4") (pintype "passive+no_connect"))
    )
    (net (code "221") (name "unconnected-(U5-IO4-Pad6)") (class "Default")
      (node (ref "U5") (pin "6") (pinfunction "IO4_6") (pintype "passive+no_connect"))
    )
  )
)
